# AJH_module_tester-v02_11.net
KiCad netlist of a schematic drawn in EAGLE
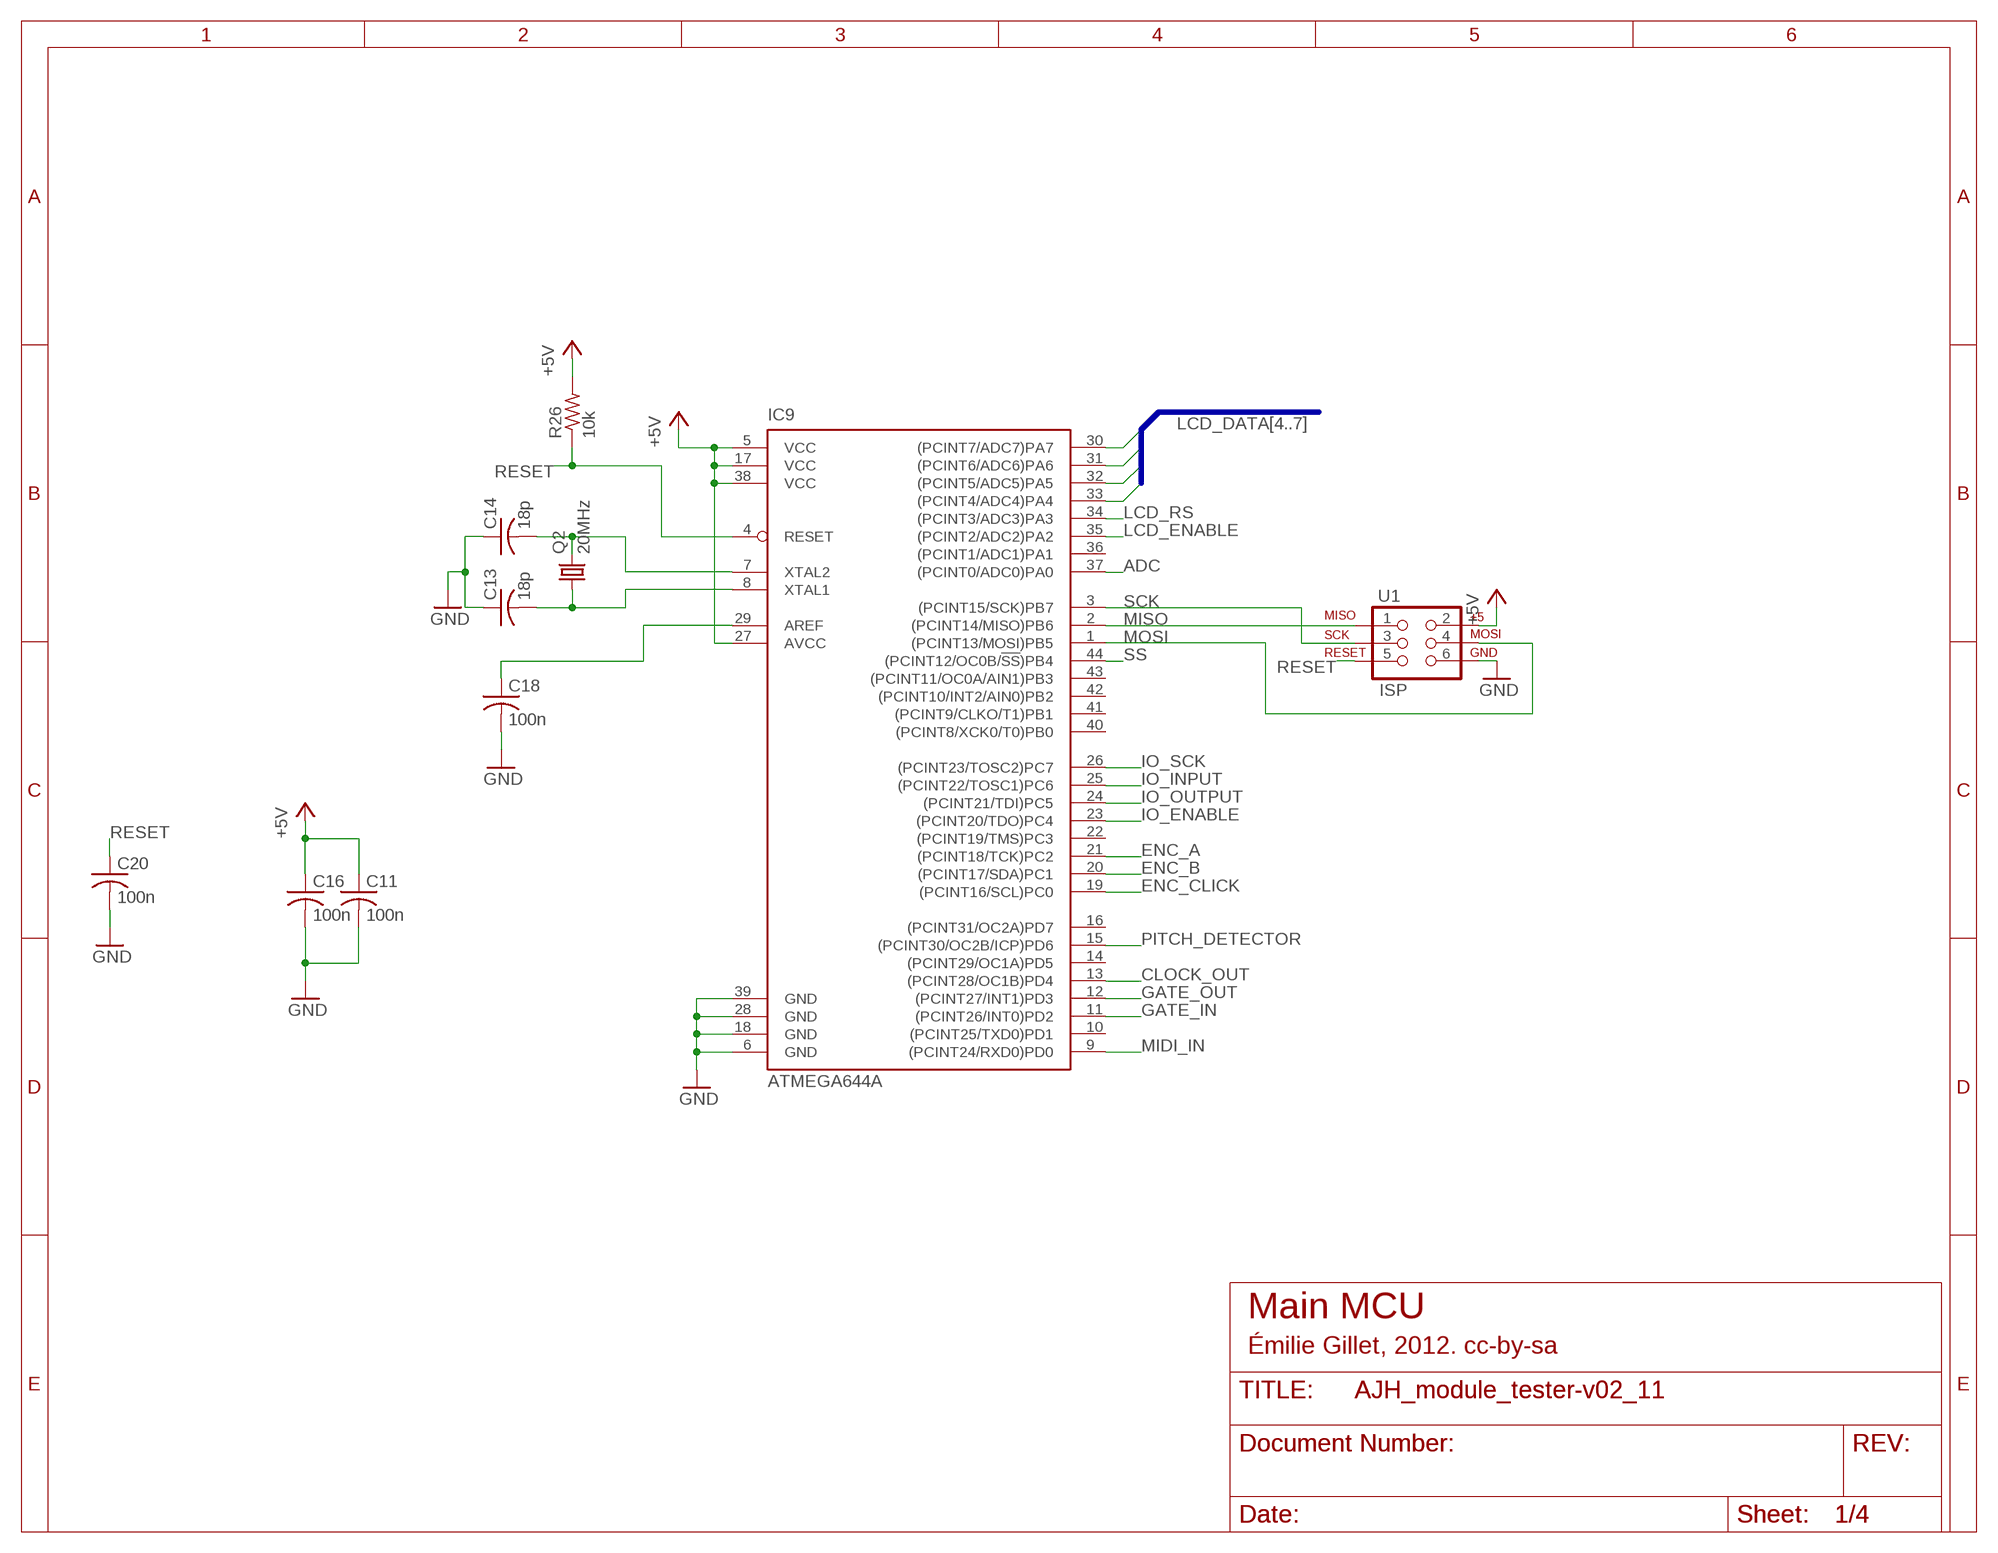
[diagram p0: schematic, sheet 1]
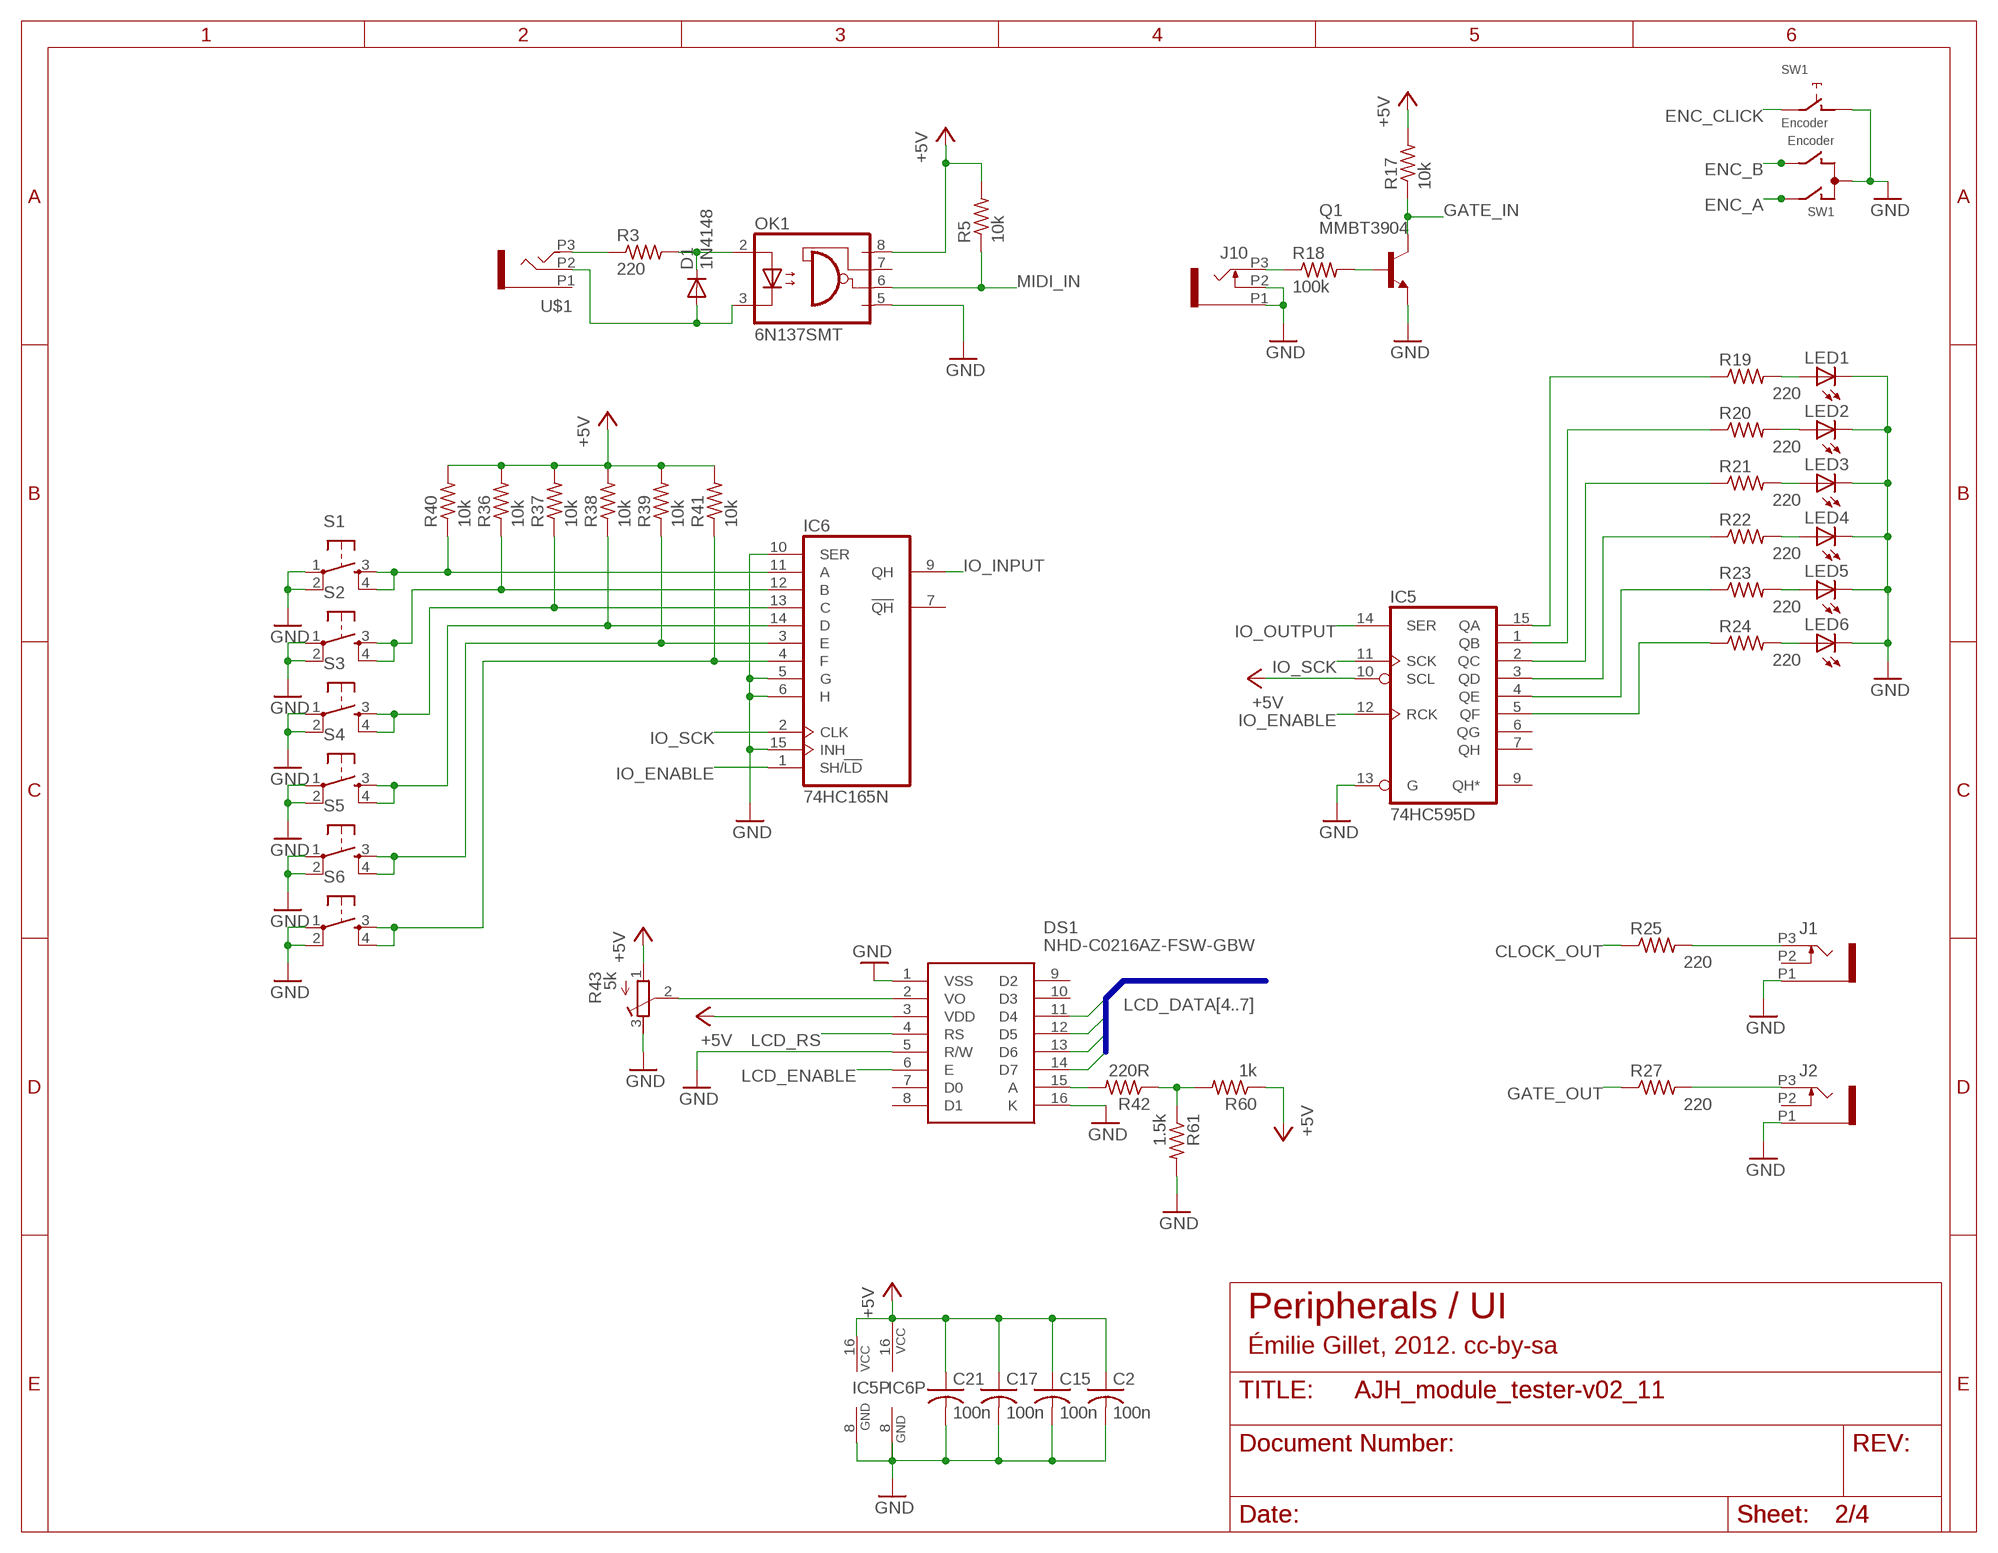
[diagram p1: schematic, sheet 2]
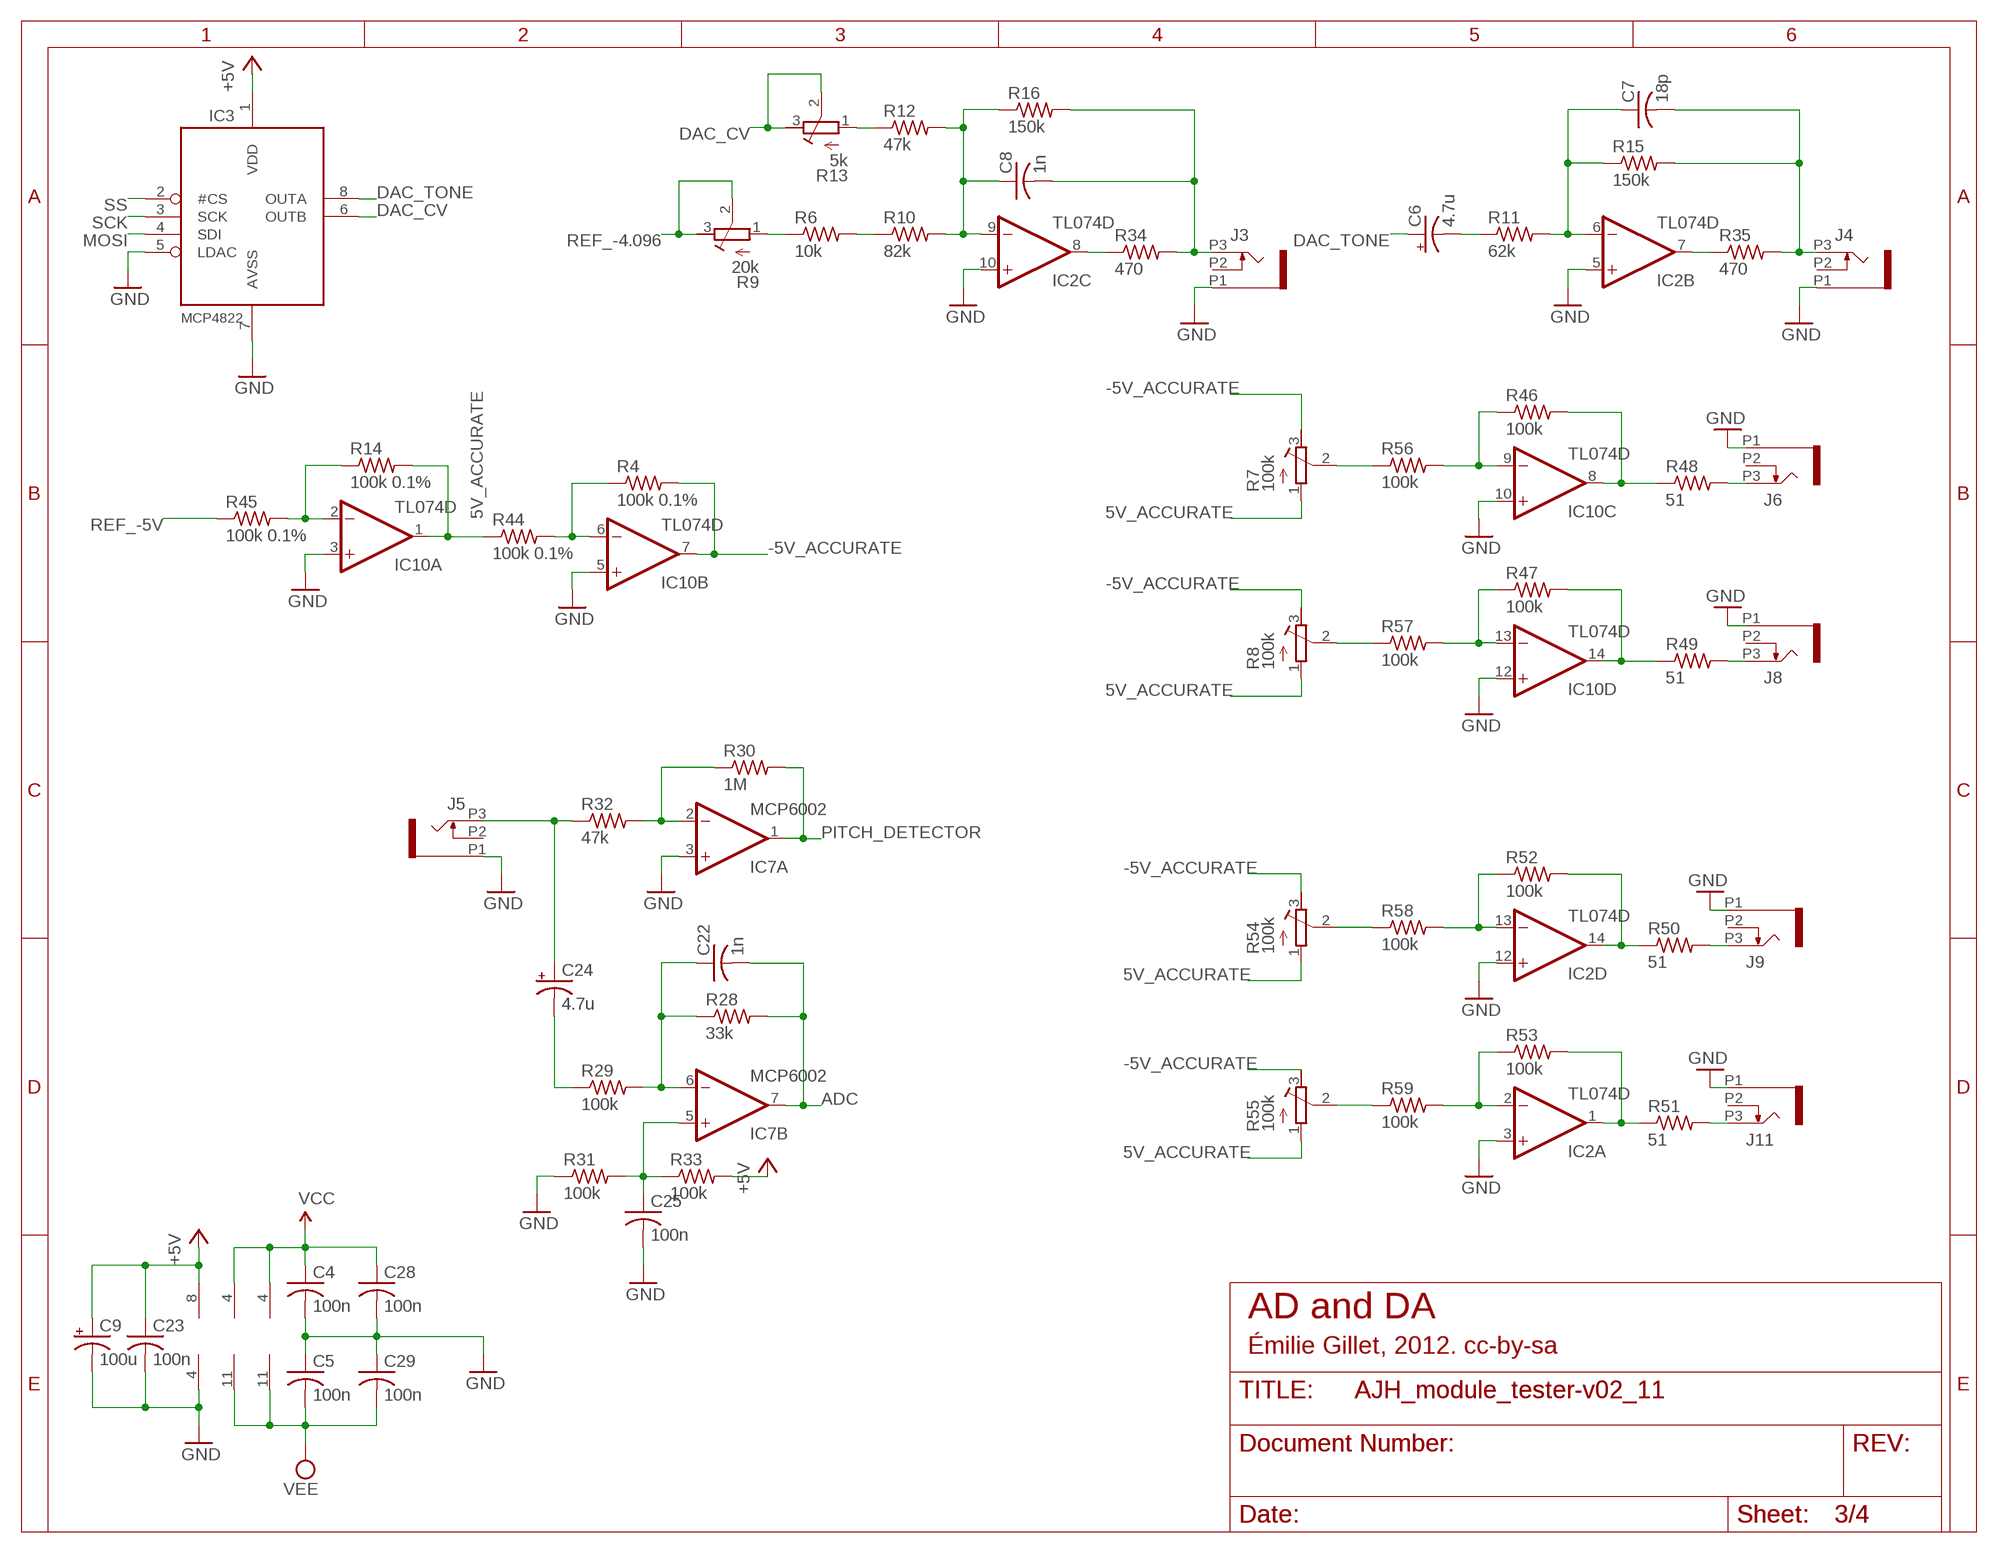
[diagram p2: schematic, sheet 3]
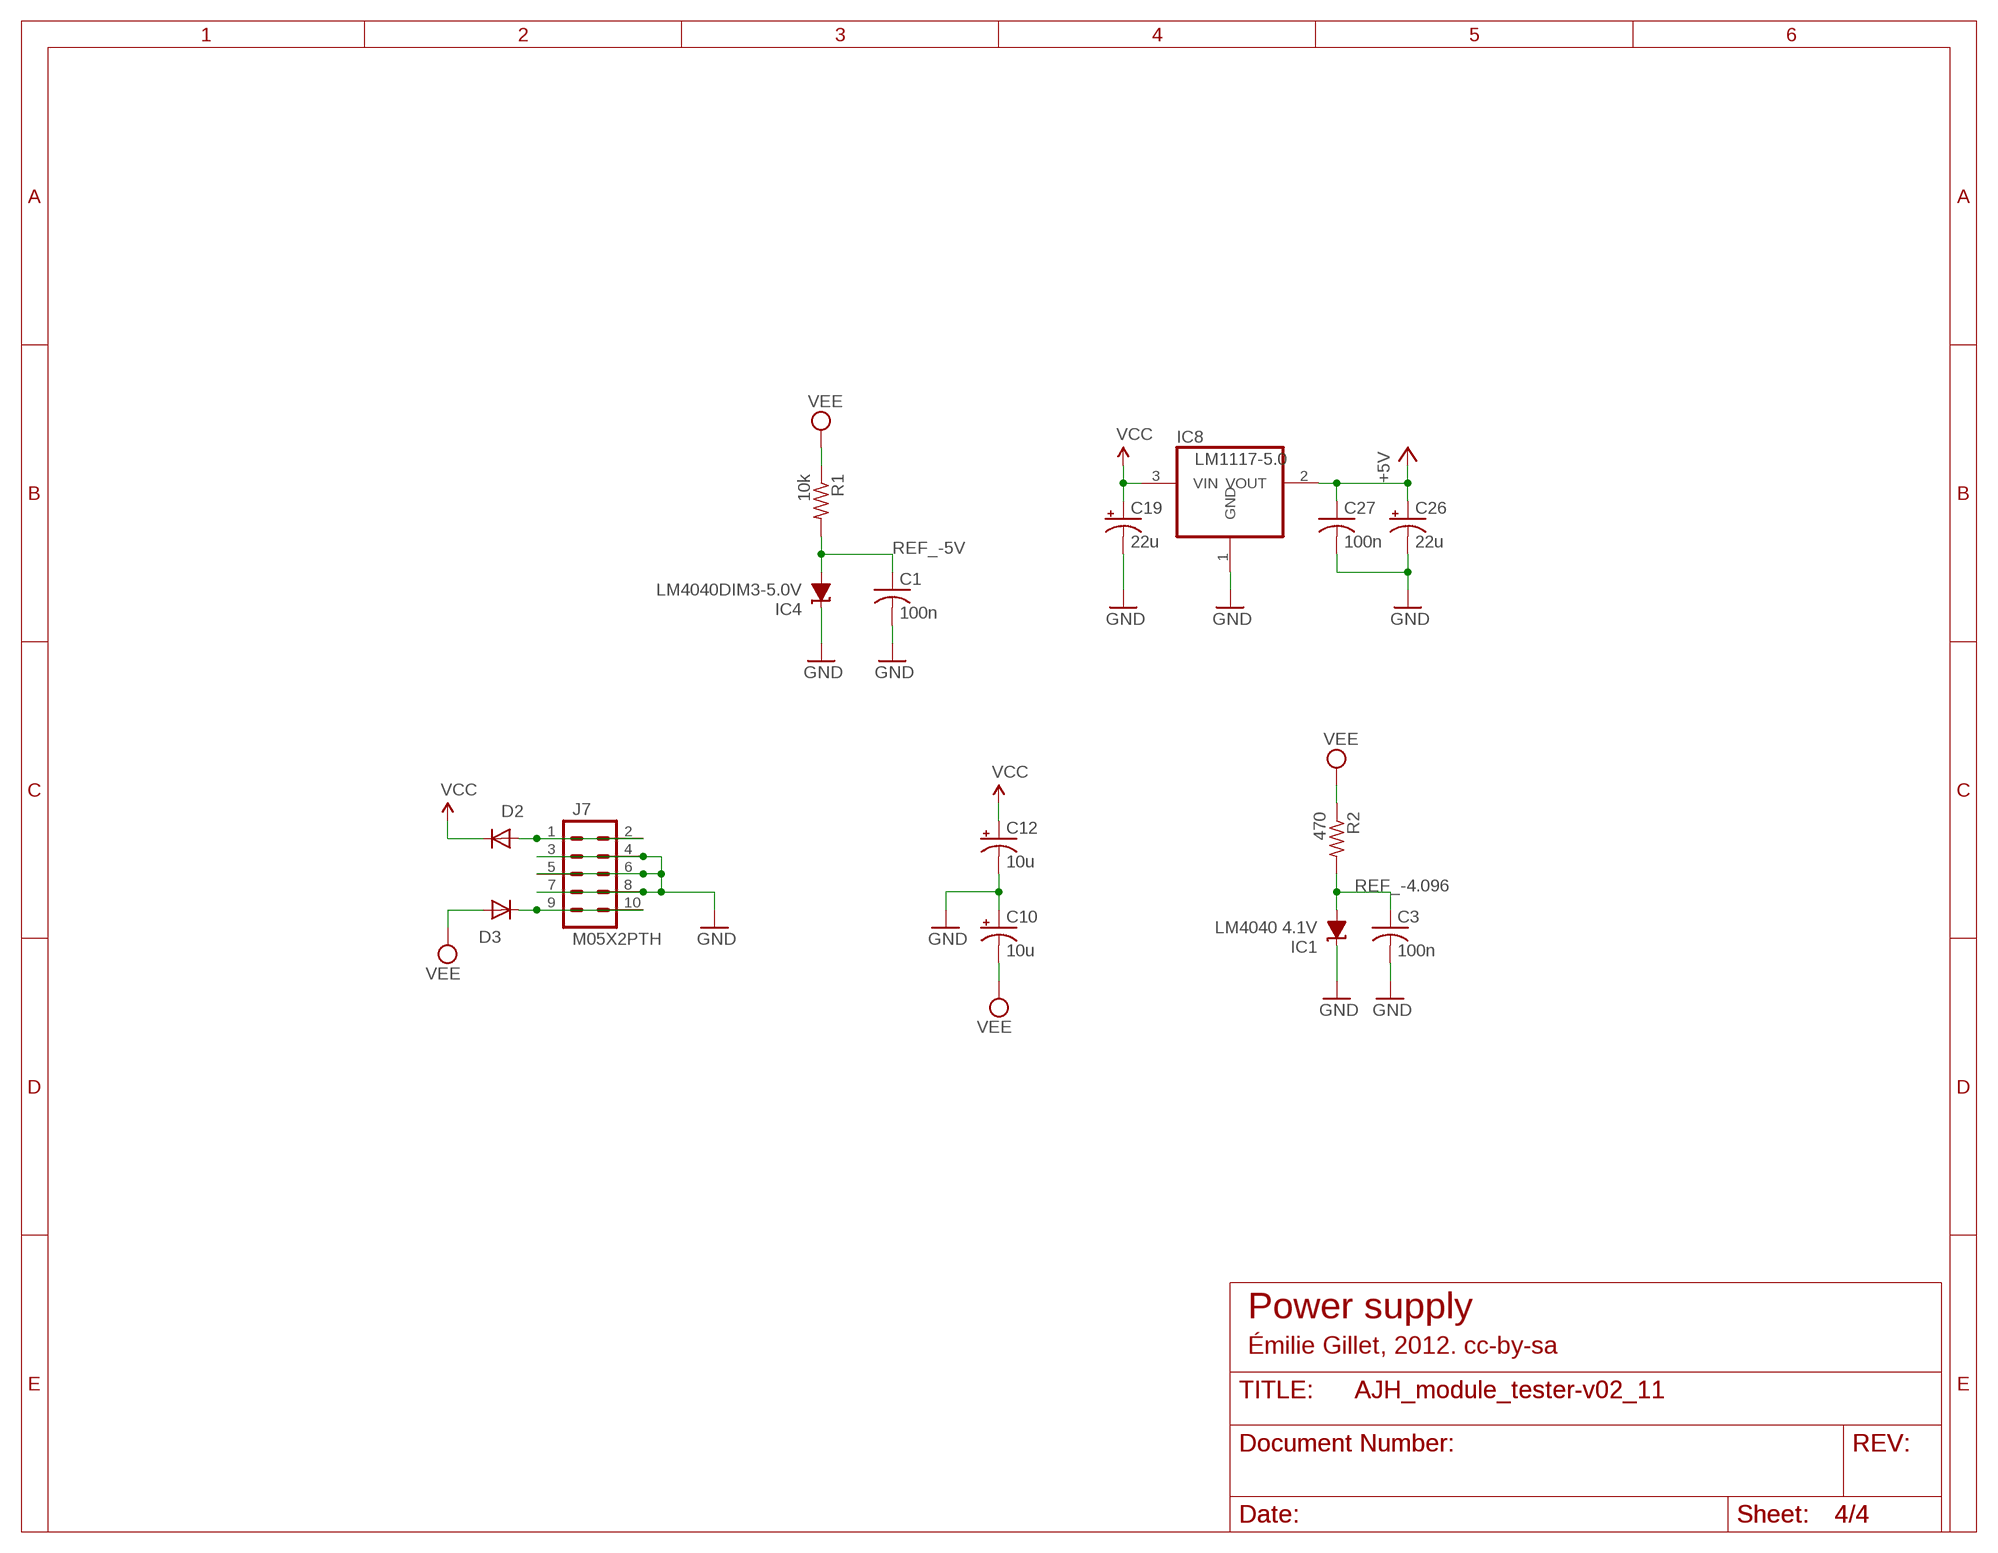
[diagram p3: schematic, sheet 4]

(export (version "E")
  (design (tool "Eeschema 10.0.6"))
  (components
    (comp (ref "C4")
      (value "100n")
      (footprint "eagle-import:C0603")
      (libsource (lib "eagle-import") (part "C-USC0603"))
    )
    (comp (ref "C5")
      (value "100n")
      (footprint "eagle-import:C0603")
      (libsource (lib "eagle-import") (part "C-USC0603"))
    )
    (comp (ref "C6")
      (value "4.7u")
      (footprint "eagle-import:PANASONIC_A")
      (libsource (lib "eagle-import") (part "CPOL-USA"))
    )
    (comp (ref "C7")
      (value "18p")
      (footprint "eagle-import:C0603")
      (libsource (lib "eagle-import") (part "C-USC0603"))
    )
    (comp (ref "C8")
      (value "1n")
      (footprint "eagle-import:C0603")
      (libsource (lib "eagle-import") (part "C-USC0603"))
    )
    (comp (ref "C9")
      (value "100u")
      (footprint "eagle-import:PANASONIC_A")
      (libsource (lib "eagle-import") (part "CPOL-USA"))
    )
    (comp (ref "C22")
      (value "1n")
      (footprint "eagle-import:C0603")
      (libsource (lib "eagle-import") (part "C-USC0603"))
    )
    (comp (ref "C23")
      (value "100n")
      (footprint "eagle-import:C0603")
      (libsource (lib "eagle-import") (part "C-USC0603"))
    )
    (comp (ref "C24")
      (value "4.7u")
      (footprint "eagle-import:PANASONIC_A")
      (libsource (lib "eagle-import") (part "CPOL-USA"))
    )
    (comp (ref "C25")
      (value "100n")
      (footprint "eagle-import:C0603")
      (libsource (lib "eagle-import") (part "C-USC0603"))
    )
    (comp (ref "C28")
      (value "100n")
      (footprint "eagle-import:C0603")
      (libsource (lib "eagle-import") (part "C-USC0603"))
    )
    (comp (ref "C29")
      (value "100n")
      (footprint "eagle-import:C0603")
      (libsource (lib "eagle-import") (part "C-USC0603"))
    )
    (comp (ref "IC2")
      (value "TL074D")
      (footprint "eagle-import:SO14")
      (libsource (lib "eagle-import") (part "TL074D"))
    )
    (comp (ref "IC3")
      (value "MCP4822SO08")
      (footprint "eagle-import:SO08")
      (libsource (lib "eagle-import") (part "MCP4822SO08"))
    )
    (comp (ref "IC7")
      (value "MCP6002")
      (footprint "eagle-import:SO08")
      (libsource (lib "eagle-import") (part "TL072D"))
    )
    (comp (ref "IC10")
      (value "TL074D")
      (footprint "eagle-import:SO14")
      (libsource (lib "eagle-import") (part "TL074D"))
    )
    (comp (ref "J3")
      (value "PJ301_THONKICONN6")
      (footprint "eagle-import:WQP_PJ_301M6")
      (libsource (lib "eagle-import") (part "PJ301_THONKICONN6"))
    )
    (comp (ref "J4")
      (value "PJ301_THONKICONN6")
      (footprint "eagle-import:WQP_PJ_301M6")
      (libsource (lib "eagle-import") (part "PJ301_THONKICONN6"))
    )
    (comp (ref "J5")
      (value "PJ301_THONKICONN6")
      (footprint "eagle-import:WQP_PJ_301M6")
      (libsource (lib "eagle-import") (part "PJ301_THONKICONN6"))
    )
    (comp (ref "J6")
      (value "PJ301_THONKICONN6")
      (footprint "eagle-import:WQP_PJ_301M6")
      (libsource (lib "eagle-import") (part "PJ301_THONKICONN6"))
    )
    (comp (ref "J8")
      (value "PJ301_THONKICONN6")
      (footprint "eagle-import:WQP_PJ_301M6")
      (libsource (lib "eagle-import") (part "PJ301_THONKICONN6"))
    )
    (comp (ref "J9")
      (value "PJ301_THONKICONN6")
      (footprint "eagle-import:WQP_PJ_301M6")
      (libsource (lib "eagle-import") (part "PJ301_THONKICONN6"))
    )
    (comp (ref "J11")
      (value "PJ301_THONKICONN6")
      (footprint "eagle-import:WQP_PJ_301M6")
      (libsource (lib "eagle-import") (part "PJ301_THONKICONN6"))
    )
    (comp (ref "R4")
      (value "100k 0.1%")
      (footprint "eagle-import:R0603")
      (libsource (lib "eagle-import") (part "R-US_R0603"))
    )
    (comp (ref "R6")
      (value "10k")
      (footprint "eagle-import:R0603")
      (libsource (lib "eagle-import") (part "R-US_R0603"))
    )
    (comp (ref "R7")
      (value "100k")
      (footprint "eagle-import:RTRIM3296W")
      (libsource (lib "eagle-import") (part "R-TRIMM3296W"))
    )
    (comp (ref "R8")
      (value "100k")
      (footprint "eagle-import:RTRIM3296W")
      (libsource (lib "eagle-import") (part "R-TRIMM3296W"))
    )
    (comp (ref "R9")
      (value "20k")
      (footprint "eagle-import:RTRIM3296W")
      (libsource (lib "eagle-import") (part "R-TRIMM3296W"))
    )
    (comp (ref "R10")
      (value "82k")
      (footprint "eagle-import:R0603")
      (libsource (lib "eagle-import") (part "R-US_R0603"))
    )
    (comp (ref "R11")
      (value "62k")
      (footprint "eagle-import:R0603")
      (libsource (lib "eagle-import") (part "R-US_R0603"))
    )
    (comp (ref "R12")
      (value "47k")
      (footprint "eagle-import:R0603")
      (libsource (lib "eagle-import") (part "R-US_R0603"))
    )
    (comp (ref "R13")
      (value "5k")
      (footprint "eagle-import:RTRIM3296W")
      (libsource (lib "eagle-import") (part "R-TRIMM3296W"))
    )
    (comp (ref "R14")
      (value "100k 0.1%")
      (footprint "eagle-import:R0603")
      (libsource (lib "eagle-import") (part "R-US_R0603"))
    )
    (comp (ref "R15")
      (value "150k")
      (footprint "eagle-import:R0603")
      (libsource (lib "eagle-import") (part "R-US_R0603"))
    )
    (comp (ref "R16")
      (value "150k")
      (footprint "eagle-import:R0603")
      (libsource (lib "eagle-import") (part "R-US_R0603"))
    )
    (comp (ref "R28")
      (value "33k")
      (footprint "eagle-import:R0603")
      (libsource (lib "eagle-import") (part "R-US_R0603"))
    )
    (comp (ref "R29")
      (value "100k")
      (footprint "eagle-import:R0603")
      (libsource (lib "eagle-import") (part "R-US_R0603"))
    )
    (comp (ref "R30")
      (value "1M")
      (footprint "eagle-import:R0603")
      (libsource (lib "eagle-import") (part "R-US_R0603"))
    )
    (comp (ref "R31")
      (value "100k")
      (footprint "eagle-import:R0603")
      (libsource (lib "eagle-import") (part "R-US_R0603"))
    )
    (comp (ref "R32")
      (value "47k")
      (footprint "eagle-import:R0603")
      (libsource (lib "eagle-import") (part "R-US_R0603"))
    )
    (comp (ref "R33")
      (value "100k")
      (footprint "eagle-import:R0603")
      (libsource (lib "eagle-import") (part "R-US_R0603"))
    )
    (comp (ref "R34")
      (value "470")
      (footprint "eagle-import:R0603")
      (libsource (lib "eagle-import") (part "R-US_R0603"))
    )
    (comp (ref "R35")
      (value "470")
      (footprint "eagle-import:R0603")
      (libsource (lib "eagle-import") (part "R-US_R0603"))
    )
    (comp (ref "R44")
      (value "100k 0.1%")
      (footprint "eagle-import:R0603")
      (libsource (lib "eagle-import") (part "R-US_R0603"))
    )
    (comp (ref "R45")
      (value "100k 0.1%")
      (footprint "eagle-import:R0603")
      (libsource (lib "eagle-import") (part "R-US_R0603"))
    )
    (comp (ref "R46")
      (value "100k")
      (footprint "eagle-import:R0603")
      (libsource (lib "eagle-import") (part "R-US_R0603"))
    )
    (comp (ref "R47")
      (value "100k")
      (footprint "eagle-import:R0603")
      (libsource (lib "eagle-import") (part "R-US_R0603"))
    )
    (comp (ref "R48")
      (value "51")
      (footprint "eagle-import:R0603")
      (libsource (lib "eagle-import") (part "R-US_R0603"))
    )
    (comp (ref "R49")
      (value "51")
      (footprint "eagle-import:R0603")
      (libsource (lib "eagle-import") (part "R-US_R0603"))
    )
    (comp (ref "R50")
      (value "51")
      (footprint "eagle-import:R0603")
      (libsource (lib "eagle-import") (part "R-US_R0603"))
    )
    (comp (ref "R51")
      (value "51")
      (footprint "eagle-import:R0603")
      (libsource (lib "eagle-import") (part "R-US_R0603"))
    )
    (comp (ref "R52")
      (value "100k")
      (footprint "eagle-import:R0603")
      (libsource (lib "eagle-import") (part "R-US_R0603"))
    )
    (comp (ref "R53")
      (value "100k")
      (footprint "eagle-import:R0603")
      (libsource (lib "eagle-import") (part "R-US_R0603"))
    )
    (comp (ref "R54")
      (value "100k")
      (footprint "eagle-import:RTRIM3296W")
      (libsource (lib "eagle-import") (part "R-TRIMM3296W"))
    )
    (comp (ref "R55")
      (value "100k")
      (footprint "eagle-import:RTRIM3296W")
      (libsource (lib "eagle-import") (part "R-TRIMM3296W"))
    )
    (comp (ref "R56")
      (value "100k")
      (footprint "eagle-import:R0603")
      (libsource (lib "eagle-import") (part "R-US_R0603"))
    )
    (comp (ref "R57")
      (value "100k")
      (footprint "eagle-import:R0603")
      (libsource (lib "eagle-import") (part "R-US_R0603"))
    )
    (comp (ref "R58")
      (value "100k")
      (footprint "eagle-import:R0603")
      (libsource (lib "eagle-import") (part "R-US_R0603"))
    )
    (comp (ref "R59")
      (value "100k")
      (footprint "eagle-import:R0603")
      (libsource (lib "eagle-import") (part "R-US_R0603"))
    )
    (comp (ref "C1")
      (value "100n")
      (footprint "eagle-import:C0603")
      (libsource (lib "eagle-import") (part "C-USC0603"))
    )
    (comp (ref "C3")
      (value "100n")
      (footprint "eagle-import:C0603")
      (libsource (lib "eagle-import") (part "C-USC0603"))
    )
    (comp (ref "C10")
      (value "10u")
      (footprint "eagle-import:PANASONIC_A")
      (libsource (lib "eagle-import") (part "CPOL-USA"))
    )
    (comp (ref "C12")
      (value "10u")
      (footprint "eagle-import:PANASONIC_A")
      (libsource (lib "eagle-import") (part "CPOL-USA"))
    )
    (comp (ref "C19")
      (value "22u")
      (footprint "eagle-import:PANASONIC_C")
      (libsource (lib "eagle-import") (part "CPOL-USC"))
    )
    (comp (ref "C26")
      (value "22u")
      (footprint "eagle-import:PANASONIC_C")
      (libsource (lib "eagle-import") (part "CPOL-USC"))
    )
    (comp (ref "C27")
      (value "100n")
      (footprint "eagle-import:C0603")
      (libsource (lib "eagle-import") (part "C-USC0603"))
    )
    (comp (ref "D2")
      (value "1N5819HW")
      (footprint "eagle-import:SOD123")
      (libsource (lib "eagle-import") (part "DIODE-SOD123"))
    )
    (comp (ref "D3")
      (value "1N5819HW")
      (footprint "eagle-import:SOD123")
      (libsource (lib "eagle-import") (part "DIODE-SOD123"))
    )
    (comp (ref "IC1")
      (value "LM4040 4.1V")
      (footprint "eagle-import:DBZ_R-PDSO-G3")
      (libsource (lib "eagle-import") (part "LM4041DBZC12"))
    )
    (comp (ref "IC4")
      (value "LM4040DIM3-5.0V")
      (footprint "eagle-import:DBZ_R-PDSO-G3")
      (libsource (lib "eagle-import") (part "LM4041DBZC12"))
    )
    (comp (ref "IC8")
      (value "LM1117-5.0")
      (footprint "eagle-import:SOT223")
      (libsource (lib "eagle-import") (part "REG1117"))
    )
    (comp (ref "J7")
      (value "M05X2PTH")
      (footprint "eagle-import:AVR_ICSP")
      (libsource (lib "eagle-import") (part "M05X2PTH"))
    )
    (comp (ref "R1")
      (value "10k")
      (footprint "eagle-import:R0603")
      (libsource (lib "eagle-import") (part "resistor_R-US_R0603"))
    )
    (comp (ref "R2")
      (value "470")
      (footprint "eagle-import:R0603")
      (libsource (lib "eagle-import") (part "resistor_R-US_R0603"))
    )
    (comp (ref "C11")
      (value "100n")
      (footprint "eagle-import:C0603")
      (libsource (lib "eagle-import") (part "C-USC0603"))
    )
    (comp (ref "C13")
      (value "18p")
      (footprint "eagle-import:C0603")
      (libsource (lib "eagle-import") (part "C-USC0603"))
    )
    (comp (ref "C14")
      (value "18p")
      (footprint "eagle-import:C0603")
      (libsource (lib "eagle-import") (part "C-USC0603"))
    )
    (comp (ref "C16")
      (value "100n")
      (footprint "eagle-import:C0603")
      (libsource (lib "eagle-import") (part "C-USC0603"))
    )
    (comp (ref "C18")
      (value "100n")
      (footprint "eagle-import:C0603")
      (libsource (lib "eagle-import") (part "C-USC0603"))
    )
    (comp (ref "C20")
      (value "100n")
      (footprint "eagle-import:C0603")
      (libsource (lib "eagle-import") (part "C-USC0603"))
    )
    (comp (ref "IC9")
      (value "ATMEGA644A")
      (footprint "eagle-import:TQFP44")
      (fields (field (name "MPN") "ATMEGA644PV-10AU"))
      (libsource (lib "eagle-import") (part "ATMEGA644A"))
    )
    (comp (ref "Q2")
      (value "20MHz")
      (footprint "eagle-import:HC49UP")
      (libsource (lib "eagle-import") (part "CRYSTALHC49UP"))
    )
    (comp (ref "R26")
      (value "10k")
      (footprint "eagle-import:R0603")
      (libsource (lib "eagle-import") (part "R-US_R0603"))
    )
    (comp (ref "U1")
      (value "ISP")
      (footprint "eagle-import:2X3")
      (libsource (lib "eagle-import") (part "AVR_SPI_PRG_6PTH"))
    )
    (comp (ref "C2")
      (value "100n")
      (footprint "eagle-import:C0603")
      (libsource (lib "eagle-import") (part "C-USC0603"))
    )
    (comp (ref "C15")
      (value "100n")
      (footprint "eagle-import:C0603")
      (libsource (lib "eagle-import") (part "C-USC0603"))
    )
    (comp (ref "C17")
      (value "100n")
      (footprint "eagle-import:C0603")
      (libsource (lib "eagle-import") (part "C-USC0603"))
    )
    (comp (ref "C21")
      (value "100n")
      (footprint "eagle-import:C0603")
      (libsource (lib "eagle-import") (part "C-USC0603"))
    )
    (comp (ref "D1")
      (value "1N4148")
      (footprint "eagle-import:SOD123")
      (libsource (lib "eagle-import") (part "DIODE-SOD123"))
    )
    (comp (ref "DS1")
      (value "NHD-C0216AZ-FSW-GBW")
      (footprint "eagle-import:NHDC0216AZFSWGBW")
      (fields (field (name "MOUSER_PART_NUMBER") "763-C0216AZ-FSW-GBW"))
      (libsource (lib "eagle-import") (part "NHD-C0216AZ-FSW-GBW"))
    )
    (comp (ref "IC5")
      (value "74HC595D")
      (footprint "eagle-import:SO16")
      (libsource (lib "eagle-import") (part "74595DHC"))
    )
    (comp (ref "IC6")
      (value "74HC165N")
      (footprint "eagle-import:SO16")
      (libsource (lib "eagle-import") (part "74165DLS"))
    )
    (comp (ref "J1")
      (value "PJ301_THONKICONN6")
      (footprint "eagle-import:WQP_PJ_301M6")
      (libsource (lib "eagle-import") (part "PJ301_THONKICONN6"))
    )
    (comp (ref "J2")
      (value "PJ301_THONKICONN6")
      (footprint "eagle-import:WQP_PJ_301M6")
      (libsource (lib "eagle-import") (part "PJ301_THONKICONN6"))
    )
    (comp (ref "J10")
      (value "PJ301_THONKICONN6")
      (footprint "eagle-import:WQP_PJ_301M6")
      (libsource (lib "eagle-import") (part "PJ301_THONKICONN6"))
    )
    (comp (ref "LED1")
      (value "LED3MM")
      (footprint "eagle-import:LED3MM")
      (libsource (lib "eagle-import") (part "LED3MM"))
    )
    (comp (ref "LED2")
      (value "LED3MM")
      (footprint "eagle-import:LED3MM")
      (libsource (lib "eagle-import") (part "LED3MM"))
    )
    (comp (ref "LED3")
      (value "LED3MM")
      (footprint "eagle-import:LED3MM")
      (libsource (lib "eagle-import") (part "LED3MM"))
    )
    (comp (ref "LED4")
      (value "LED3MM")
      (footprint "eagle-import:LED3MM")
      (libsource (lib "eagle-import") (part "LED3MM"))
    )
    (comp (ref "LED5")
      (value "LED3MM")
      (footprint "eagle-import:LED3MM")
      (libsource (lib "eagle-import") (part "LED3MM"))
    )
    (comp (ref "LED6")
      (value "LED3MM")
      (footprint "eagle-import:LED3MM")
      (libsource (lib "eagle-import") (part "LED3MM"))
    )
    (comp (ref "OK1")
      (value "6N137SMT")
      (footprint "eagle-import:DIL8-SMD")
      (libsource (lib "eagle-import") (part "6N137SMT"))
    )
    (comp (ref "Q1")
      (value "MMBT3904")
      (footprint "eagle-import:SOT23-BEC")
      (libsource (lib "eagle-import") (part "-NPN-SOT23-BECMMBT3904LT1"))
    )
    (comp (ref "R3")
      (value "220")
      (footprint "eagle-import:R0603")
      (libsource (lib "eagle-import") (part "R-US_R0603"))
    )
    (comp (ref "R5")
      (value "10k")
      (footprint "eagle-import:R0603")
      (libsource (lib "eagle-import") (part "R-US_R0603"))
    )
    (comp (ref "R17")
      (value "10k")
      (footprint "eagle-import:R0603")
      (libsource (lib "eagle-import") (part "R-US_R0603"))
    )
    (comp (ref "R18")
      (value "100k")
      (footprint "eagle-import:R0603")
      (libsource (lib "eagle-import") (part "R-US_R0603"))
    )
    (comp (ref "R19")
      (value "220")
      (footprint "eagle-import:R0603")
      (libsource (lib "eagle-import") (part "R-US_R0603"))
    )
    (comp (ref "R20")
      (value "220")
      (footprint "eagle-import:R0603")
      (libsource (lib "eagle-import") (part "R-US_R0603"))
    )
    (comp (ref "R21")
      (value "220")
      (footprint "eagle-import:R0603")
      (libsource (lib "eagle-import") (part "R-US_R0603"))
    )
    (comp (ref "R22")
      (value "220")
      (footprint "eagle-import:R0603")
      (libsource (lib "eagle-import") (part "R-US_R0603"))
    )
    (comp (ref "R23")
      (value "220")
      (footprint "eagle-import:R0603")
      (libsource (lib "eagle-import") (part "R-US_R0603"))
    )
    (comp (ref "R24")
      (value "220")
      (footprint "eagle-import:R0603")
      (libsource (lib "eagle-import") (part "R-US_R0603"))
    )
    (comp (ref "R25")
      (value "220")
      (footprint "eagle-import:R0603")
      (libsource (lib "eagle-import") (part "R-US_R0603"))
    )
    (comp (ref "R27")
      (value "220")
      (footprint "eagle-import:R0603")
      (libsource (lib "eagle-import") (part "R-US_R0603"))
    )
    (comp (ref "R36")
      (value "10k")
      (footprint "eagle-import:R0603")
      (libsource (lib "eagle-import") (part "R-US_R0603"))
    )
    (comp (ref "R37")
      (value "10k")
      (footprint "eagle-import:R0603")
      (libsource (lib "eagle-import") (part "R-US_R0603"))
    )
    (comp (ref "R38")
      (value "10k")
      (footprint "eagle-import:R0603")
      (libsource (lib "eagle-import") (part "R-US_R0603"))
    )
    (comp (ref "R39")
      (value "10k")
      (footprint "eagle-import:R0603")
      (libsource (lib "eagle-import") (part "R-US_R0603"))
    )
    (comp (ref "R40")
      (value "10k")
      (footprint "eagle-import:R0603")
      (libsource (lib "eagle-import") (part "R-US_R0603"))
    )
    (comp (ref "R41")
      (value "10k")
      (footprint "eagle-import:R0603")
      (libsource (lib "eagle-import") (part "R-US_R0603"))
    )
    (comp (ref "R42")
      (value "220R")
      (footprint "eagle-import:R0603")
      (libsource (lib "eagle-import") (part "R-US_R0603"))
    )
    (comp (ref "R43")
      (value "5k")
      (footprint "eagle-import:RTRIM3339P")
      (libsource (lib "eagle-import") (part "R-TRIMM3339P"))
    )
    (comp (ref "R60")
      (value "1k")
      (footprint "eagle-import:R0603")
      (libsource (lib "eagle-import") (part "R-US_R0603"))
    )
    (comp (ref "R61")
      (value "1.5k")
      (footprint "eagle-import:R0603")
      (libsource (lib "eagle-import") (part "R-US_R0603"))
    )
    (comp (ref "S1")
      (value "TAC_SWITCHPTH")
      (footprint "eagle-import:TACTILE-PTH")
      (libsource (lib "eagle-import") (part "TAC_SWITCHPTH"))
    )
    (comp (ref "S2")
      (value "TAC_SWITCHPTH")
      (footprint "eagle-import:TACTILE-PTH")
      (libsource (lib "eagle-import") (part "TAC_SWITCHPTH"))
    )
    (comp (ref "S3")
      (value "TAC_SWITCHPTH")
      (footprint "eagle-import:TACTILE-PTH")
      (libsource (lib "eagle-import") (part "TAC_SWITCHPTH"))
    )
    (comp (ref "S4")
      (value "TAC_SWITCHPTH")
      (footprint "eagle-import:TACTILE-PTH")
      (libsource (lib "eagle-import") (part "TAC_SWITCHPTH"))
    )
    (comp (ref "S5")
      (value "TAC_SWITCHPTH")
      (footprint "eagle-import:TACTILE-PTH")
      (libsource (lib "eagle-import") (part "TAC_SWITCHPTH"))
    )
    (comp (ref "S6")
      (value "TAC_SWITCHPTH")
      (footprint "eagle-import:TACTILE-PTH")
      (libsource (lib "eagle-import") (part "TAC_SWITCHPTH"))
    )
    (comp (ref "SW1")
      (value "Encoder")
      (footprint "eagle-import:ALPS_EC12E_SW")
      (libsource (lib "eagle-import") (part "EC12E_SW"))
    )
    (comp (ref "U$1")
      (value "PJ366ST")
      (footprint "eagle-import:WQP_PJ_301M8")
      (libsource (lib "eagle-import") (part "PJ366ST"))
    )
  )
  (nets
    (net (code "1") (name "+5V") (class "Default")
      (node (ref "C11") (pin "1") (pinfunction "1_1") (pintype "passive"))
      (node (ref "C15") (pin "1") (pinfunction "1_1") (pintype "passive"))
      (node (ref "C16") (pin "1") (pinfunction "1_1") (pintype "passive"))
      (node (ref "C17") (pin "1") (pinfunction "1_1") (pintype "passive"))
      (node (ref "C2") (pin "1") (pinfunction "1_1") (pintype "passive"))
      (node (ref "C21") (pin "1") (pinfunction "1_1") (pintype "passive"))
      (node (ref "C23") (pin "1") (pinfunction "1_1") (pintype "passive"))
      (node (ref "C26") (pin "+") (pinfunction "+_+") (pintype "passive"))
      (node (ref "C27") (pin "1") (pinfunction "1_1") (pintype "passive"))
      (node (ref "C9") (pin "+") (pinfunction "+_+") (pintype "passive"))
      (node (ref "DS1") (pin "3") (pinfunction "VDD_3") (pintype "bidirectional"))
      (node (ref "IC3") (pin "1") (pinfunction "VDD_1") (pintype "power_in"))
      (node (ref "IC5") (pin "10") (pinfunction "SCL_10") (pintype "input"))
      (node (ref "IC5") (pin "16") (pinfunction "VCC_16") (pintype "power_in"))
      (node (ref "IC6") (pin "16") (pinfunction "VCC_16") (pintype "power_in"))
      (node (ref "IC7") (pin "8") (pinfunction "V+_8") (pintype "power_in"))
      (node (ref "IC8") (pin "2") (pinfunction "VOUT_2") (pintype "output"))
      (node (ref "IC9") (pin "17") (pinfunction "VCC_17") (pintype "power_in"))
      (node (ref "IC9") (pin "27") (pinfunction "AVCC_27") (pintype "power_in"))
      (node (ref "IC9") (pin "38") (pinfunction "VCC_38") (pintype "power_in"))
      (node (ref "IC9") (pin "5") (pinfunction "VCC_5") (pintype "power_in"))
      (node (ref "OK1") (pin "8") (pinfunction "VCC_8") (pintype "passive"))
      (node (ref "R17") (pin "2") (pinfunction "2_2") (pintype "passive"))
      (node (ref "R26") (pin "2") (pinfunction "2_2") (pintype "passive"))
      (node (ref "R33") (pin "2") (pinfunction "2_2") (pintype "passive"))
      (node (ref "R36") (pin "2") (pinfunction "2_2") (pintype "passive"))
      (node (ref "R37") (pin "2") (pinfunction "2_2") (pintype "passive"))
      (node (ref "R38") (pin "2") (pinfunction "2_2") (pintype "passive"))
      (node (ref "R39") (pin "2") (pinfunction "2_2") (pintype "passive"))
      (node (ref "R40") (pin "2") (pinfunction "2_2") (pintype "passive"))
      (node (ref "R41") (pin "2") (pinfunction "2_2") (pintype "passive"))
      (node (ref "R43") (pin "1") (pinfunction "E_1") (pintype "passive"))
      (node (ref "R5") (pin "2") (pinfunction "2_2") (pintype "passive"))
      (node (ref "R60") (pin "1") (pinfunction "1_1") (pintype "passive"))
      (node (ref "U1") (pin "2") (pinfunction "2_2") (pintype "passive"))
    )
    (net (code "2") (name "-5V_ACCURATE") (class "Default")
      (node (ref "IC10") (pin "7") (pinfunction "OUT_7") (pintype "output"))
      (node (ref "R4") (pin "2") (pinfunction "2_2") (pintype "passive"))
      (node (ref "R54") (pin "3") (pinfunction "A_3") (pintype "passive"))
      (node (ref "R55") (pin "3") (pinfunction "A_3") (pintype "passive"))
      (node (ref "R7") (pin "3") (pinfunction "A_3") (pintype "passive"))
      (node (ref "R8") (pin "3") (pinfunction "A_3") (pintype "passive"))
    )
    (net (code "5") (name "5V_ACCURATE") (class "Default")
      (node (ref "IC10") (pin "1") (pinfunction "OUT_1") (pintype "output"))
      (node (ref "R14") (pin "2") (pinfunction "2_2") (pintype "passive"))
      (node (ref "R44") (pin "1") (pinfunction "1_1") (pintype "passive"))
      (node (ref "R54") (pin "1") (pinfunction "E_1") (pintype "passive"))
      (node (ref "R55") (pin "1") (pinfunction "E_1") (pintype "passive"))
      (node (ref "R7") (pin "1") (pinfunction "E_1") (pintype "passive"))
      (node (ref "R8") (pin "1") (pinfunction "E_1") (pintype "passive"))
    )
    (net (code "6") (name "ADC") (class "Default")
      (node (ref "C22") (pin "2") (pinfunction "2_2") (pintype "passive"))
      (node (ref "IC7") (pin "7") (pinfunction "OUT_7") (pintype "output"))
      (node (ref "IC9") (pin "37") (pinfunction "(PCINT0/ADC0)PA0_37") (pintype "bidirectional"))
      (node (ref "R28") (pin "2") (pinfunction "2_2") (pintype "passive"))
    )
    (net (code "7") (name "CLOCK_OUT") (class "Default")
      (node (ref "IC9") (pin "13") (pinfunction "(PCINT28/OC1B)PD4_13") (pintype "bidirectional"))
      (node (ref "R25") (pin "1") (pinfunction "1_1") (pintype "passive"))
    )
    (net (code "8") (name "DAC_CV") (class "Default")
      (node (ref "IC3") (pin "6") (pinfunction "OUTB_6") (pintype "output"))
      (node (ref "R13") (pin "2") (pinfunction "S_2") (pintype "passive"))
      (node (ref "R13") (pin "3") (pinfunction "A_3") (pintype "passive"))
    )
    (net (code "9") (name "DAC_TONE") (class "Default")
      (node (ref "C6") (pin "+") (pinfunction "+_+") (pintype "passive"))
      (node (ref "IC3") (pin "8") (pinfunction "OUTA_8") (pintype "output"))
    )
    (net (code "10") (name "ENC_A") (class "Default")
      (node (ref "IC9") (pin "21") (pinfunction "(PCINT18/TCK)PC2_21") (pintype "output"))
      (node (ref "SW1") (pin "A") (pinfunction "A_A") (pintype "passive"))
    )
    (net (code "11") (name "ENC_B") (class "Default")
      (node (ref "IC9") (pin "20") (pinfunction "(PCINT17/SDA)PC1_20") (pintype "output"))
      (node (ref "SW1") (pin "B") (pinfunction "B_B") (pintype "passive"))
    )
    (net (code "12") (name "ENC_CLICK") (class "Default")
      (node (ref "IC9") (pin "19") (pinfunction "(PCINT16/SCL)PC0_19") (pintype "output"))
      (node (ref "SW1") (pin "E") (pinfunction "2_E") (pintype "passive"))
    )
    (net (code "13") (name "GATE_IN") (class "Default")
      (node (ref "IC9") (pin "11") (pinfunction "(PCINT26/INT0)PD2_11") (pintype "bidirectional"))
      (node (ref "Q1") (pin "C") (pinfunction "C_C") (pintype "passive"))
      (node (ref "R17") (pin "1") (pinfunction "1_1") (pintype "passive"))
    )
    (net (code "14") (name "GATE_OUT") (class "Default")
      (node (ref "IC9") (pin "12") (pinfunction "(PCINT27/INT1)PD3_12") (pintype "bidirectional"))
      (node (ref "R27") (pin "1") (pinfunction "1_1") (pintype "passive"))
    )
    (net (code "15") (name "GND") (class "Default")
      (node (ref "C1") (pin "2") (pinfunction "2_2") (pintype "passive"))
      (node (ref "C10") (pin "+") (pinfunction "+_+") (pintype "passive"))
      (node (ref "C11") (pin "2") (pinfunction "2_2") (pintype "passive"))
      (node (ref "C12") (pin "-") (pinfunction "-_-") (pintype "passive"))
      (node (ref "C13") (pin "1") (pinfunction "1_1") (pintype "passive"))
      (node (ref "C14") (pin "1") (pinfunction "1_1") (pintype "passive"))
      (node (ref "C15") (pin "2") (pinfunction "2_2") (pintype "passive"))
      (node (ref "C16") (pin "2") (pinfunction "2_2") (pintype "passive"))
      (node (ref "C17") (pin "2") (pinfunction "2_2") (pintype "passive"))
      (node (ref "C18") (pin "2") (pinfunction "2_2") (pintype "passive"))
      (node (ref "C19") (pin "-") (pinfunction "-_-") (pintype "passive"))
      (node (ref "C2") (pin "2") (pinfunction "2_2") (pintype "passive"))
      (node (ref "C20") (pin "2") (pinfunction "2_2") (pintype "passive"))
      (node (ref "C21") (pin "2") (pinfunction "2_2") (pintype "passive"))
      (node (ref "C23") (pin "2") (pinfunction "2_2") (pintype "passive"))
      (node (ref "C25") (pin "2") (pinfunction "2_2") (pintype "passive"))
      (node (ref "C26") (pin "-") (pinfunction "-_-") (pintype "passive"))
      (node (ref "C27") (pin "2") (pinfunction "2_2") (pintype "passive"))
      (node (ref "C28") (pin "2") (pinfunction "2_2") (pintype "passive"))
      (node (ref "C29") (pin "1") (pinfunction "1_1") (pintype "passive"))
      (node (ref "C3") (pin "2") (pinfunction "2_2") (pintype "passive"))
      (node (ref "C4") (pin "2") (pinfunction "2_2") (pintype "passive"))
      (node (ref "C5") (pin "1") (pinfunction "1_1") (pintype "passive"))
      (node (ref "C9") (pin "-") (pinfunction "-_-") (pintype "passive"))
      (node (ref "DS1") (pin "1") (pinfunction "VSS_1") (pintype "bidirectional"))
      (node (ref "DS1") (pin "16") (pinfunction "K_16") (pintype "bidirectional"))
      (node (ref "DS1") (pin "5") (pinfunction "R/W_5") (pintype "bidirectional"))
      (node (ref "IC1") (pin "1") (pinfunction "C_1") (pintype "passive"))
      (node (ref "IC10") (pin "10") (pinfunction "+IN_10") (pintype "input"))
      (node (ref "IC10") (pin "12") (pinfunction "+IN_12") (pintype "input"))
      (node (ref "IC10") (pin "3") (pinfunction "+IN_3") (pintype "input"))
      (node (ref "IC10") (pin "5") (pinfunction "+IN_5") (pintype "input"))
      (node (ref "IC2") (pin "10") (pinfunction "+IN_10") (pintype "input"))
      (node (ref "IC2") (pin "12") (pinfunction "+IN_12") (pintype "input"))
      (node (ref "IC2") (pin "3") (pinfunction "+IN_3") (pintype "input"))
      (node (ref "IC2") (pin "5") (pinfunction "+IN_5") (pintype "input"))
      (node (ref "IC3") (pin "5") (pinfunction "LDAC_5") (pintype "input"))
      (node (ref "IC3") (pin "7") (pinfunction "AVSS_7") (pintype "power_in"))
      (node (ref "IC4") (pin "1") (pinfunction "C_1") (pintype "passive"))
      (node (ref "IC5") (pin "13") (pinfunction "G_13") (pintype "input"))
      (node (ref "IC5") (pin "8") (pinfunction "GND_8") (pintype "power_in"))
      (node (ref "IC6") (pin "10") (pinfunction "SER_10") (pintype "input"))
      (node (ref "IC6") (pin "15") (pinfunction "INH_15") (pintype "input"))
      (node (ref "IC6") (pin "5") (pinfunction "G_5") (pintype "input"))
      (node (ref "IC6") (pin "6") (pinfunction "H_6") (pintype "input"))
      (node (ref "IC6") (pin "8") (pinfunction "GND_8") (pintype "power_in"))
      (node (ref "IC7") (pin "3") (pinfunction "+IN_3") (pintype "input"))
      (node (ref "IC7") (pin "4") (pinfunction "V-_4") (pintype "power_in"))
      (node (ref "IC8") (pin "1") (pinfunction "GND_1") (pintype "power_in"))
      (node (ref "IC9") (pin "18") (pinfunction "GND_18") (pintype "power_in"))
      (node (ref "IC9") (pin "28") (pinfunction "GND_28") (pintype "power_in"))
      (node (ref "IC9") (pin "39") (pinfunction "GND_39") (pintype "power_in"))
      (node (ref "IC9") (pin "6") (pinfunction "GND_6") (pintype "power_in"))
      (node (ref "J1") (pin "P1") (pinfunction "1_P1") (pintype "passive"))
      (node (ref "J10") (pin "P1") (pinfunction "1_P1") (pintype "passive"))
      (node (ref "J10") (pin "P2") (pinfunction "2_P2") (pintype "passive"))
      (node (ref "J11") (pin "P1") (pinfunction "1_P1") (pintype "passive"))
      (node (ref "J2") (pin "P1") (pinfunction "1_P1") (pintype "passive"))
      (node (ref "J3") (pin "P1") (pinfunction "1_P1") (pintype "passive"))
      (node (ref "J4") (pin "P1") (pinfunction "1_P1") (pintype "passive"))
      (node (ref "J5") (pin "P1") (pinfunction "1_P1") (pintype "passive"))
      (node (ref "J6") (pin "P1") (pinfunction "1_P1") (pintype "passive"))
      (node (ref "J7") (pin "3") (pinfunction "3_3") (pintype "passive"))
      (node (ref "J7") (pin "4") (pinfunction "4_4") (pintype "passive"))
      (node (ref "J7") (pin "5") (pinfunction "5_5") (pintype "passive"))
      (node (ref "J7") (pin "6") (pinfunction "6_6") (pintype "passive"))
      (node (ref "J7") (pin "7") (pinfunction "7_7") (pintype "passive"))
      (node (ref "J7") (pin "8") (pinfunction "8_8") (pintype "passive"))
      (node (ref "J8") (pin "P1") (pinfunction "1_P1") (pintype "passive"))
      (node (ref "J9") (pin "P1") (pinfunction "1_P1") (pintype "passive"))
      (node (ref "LED1") (pin "K") (pinfunction "C_K") (pintype "passive"))
      (node (ref "LED2") (pin "K") (pinfunction "C_K") (pintype "passive"))
      (node (ref "LED3") (pin "K") (pinfunction "C_K") (pintype "passive"))
      (node (ref "LED4") (pin "K") (pinfunction "C_K") (pintype "passive"))
      (node (ref "LED5") (pin "K") (pinfunction "C_K") (pintype "passive"))
      (node (ref "LED6") (pin "K") (pinfunction "C_K") (pintype "passive"))
      (node (ref "OK1") (pin "5") (pinfunction "GND_5") (pintype "passive"))
      (node (ref "Q1") (pin "E") (pinfunction "E_E") (pintype "passive"))
      (node (ref "R31") (pin "1") (pinfunction "1_1") (pintype "passive"))
      (node (ref "R43") (pin "3") (pinfunction "A_3") (pintype "passive"))
      (node (ref "R61") (pin "2") (pinfunction "2_2") (pintype "passive"))
      (node (ref "S1") (pin "1") (pinfunction "1_1") (pintype "passive"))
      (node (ref "S1") (pin "2") (pinfunction "2_2") (pintype "passive"))
      (node (ref "S2") (pin "1") (pinfunction "1_1") (pintype "passive"))
      (node (ref "S2") (pin "2") (pinfunction "2_2") (pintype "passive"))
      (node (ref "S3") (pin "1") (pinfunction "1_1") (pintype "passive"))
      (node (ref "S3") (pin "2") (pinfunction "2_2") (pintype "passive"))
      (node (ref "S4") (pin "1") (pinfunction "1_1") (pintype "passive"))
      (node (ref "S4") (pin "2") (pinfunction "2_2") (pintype "passive"))
      (node (ref "S5") (pin "1") (pinfunction "1_1") (pintype "passive"))
      (node (ref "S5") (pin "2") (pinfunction "2_2") (pintype "passive"))
      (node (ref "S6") (pin "1") (pinfunction "1_1") (pintype "passive"))
      (node (ref "S6") (pin "2") (pinfunction "2_2") (pintype "passive"))
      (node (ref "SW1") (pin "C") (pinfunction "C_C") (pintype "passive"))
      (node (ref "SW1") (pin "D") (pinfunction "1_D") (pintype "passive"))
      (node (ref "U1") (pin "6") (pinfunction "6_6") (pintype "passive"))
    )
    (net (code "16") (name "IO_ENABLE") (class "Default")
      (node (ref "IC5") (pin "12") (pinfunction "RCK_12") (pintype "input"))
      (node (ref "IC6") (pin "1") (pinfunction "SH/~{LD}_1") (pintype "input"))
      (node (ref "IC9") (pin "23") (pinfunction "(PCINT20/TDO)PC4_23") (pintype "output"))
    )
    (net (code "17") (name "IO_INPUT") (class "Default")
      (node (ref "IC6") (pin "9") (pinfunction "QH_9") (pintype "output"))
      (node (ref "IC9") (pin "25") (pinfunction "(PCINT22/TOSC1)PC6_25") (pintype "output"))
    )
    (net (code "18") (name "IO_OUTPUT") (class "Default")
      (node (ref "IC5") (pin "14") (pinfunction "SER_14") (pintype "input"))
      (node (ref "IC9") (pin "24") (pinfunction "(PCINT21/TDI)PC5_24") (pintype "output"))
    )
    (net (code "19") (name "IO_SCK") (class "Default")
      (node (ref "IC5") (pin "11") (pinfunction "SCK_11") (pintype "input"))
      (node (ref "IC6") (pin "2") (pinfunction "CLK_2") (pintype "input"))
      (node (ref "IC9") (pin "26") (pinfunction "(PCINT23/TOSC2)PC7_26") (pintype "output"))
    )
    (net (code "20") (name "LCD_DATA4") (class "Default")
      (node (ref "DS1") (pin "11") (pinfunction "D4_11") (pintype "bidirectional"))
      (node (ref "IC9") (pin "33") (pinfunction "(PCINT4/ADC4)PA4_33") (pintype "bidirectional"))
    )
    (net (code "21") (name "LCD_DATA5") (class "Default")
      (node (ref "DS1") (pin "12") (pinfunction "D5_12") (pintype "bidirectional"))
      (node (ref "IC9") (pin "32") (pinfunction "(PCINT5/ADC5)PA5_32") (pintype "bidirectional"))
    )
    (net (code "22") (name "LCD_DATA6") (class "Default")
      (node (ref "DS1") (pin "13") (pinfunction "D6_13") (pintype "bidirectional"))
      (node (ref "IC9") (pin "31") (pinfunction "(PCINT6/ADC6)PA6_31") (pintype "bidirectional"))
    )
    (net (code "23") (name "LCD_DATA7") (class "Default")
      (node (ref "DS1") (pin "14") (pinfunction "D7_14") (pintype "bidirectional"))
      (node (ref "IC9") (pin "30") (pinfunction "(PCINT7/ADC7)PA7_30") (pintype "bidirectional"))
    )
    (net (code "24") (name "LCD_ENABLE") (class "Default")
      (node (ref "DS1") (pin "6") (pinfunction "E_6") (pintype "bidirectional"))
      (node (ref "IC9") (pin "35") (pinfunction "(PCINT2/ADC2)PA2_35") (pintype "bidirectional"))
    )
    (net (code "25") (name "LCD_RS") (class "Default")
      (node (ref "DS1") (pin "4") (pinfunction "RS_4") (pintype "bidirectional"))
      (node (ref "IC9") (pin "34") (pinfunction "(PCINT3/ADC3)PA3_34") (pintype "bidirectional"))
    )
    (net (code "26") (name "MIDI_IN") (class "Default")
      (node (ref "IC9") (pin "9") (pinfunction "(PCINT24/RXD0)PD0_9") (pintype "bidirectional"))
      (node (ref "OK1") (pin "6") (pinfunction "VO_6") (pintype "passive"))
      (node (ref "R5") (pin "1") (pinfunction "1_1") (pintype "passive"))
    )
    (net (code "27") (name "MISO") (class "Default")
      (node (ref "IC9") (pin "2") (pinfunction "(PCINT14/MISO)PB6_2") (pintype "bidirectional"))
      (node (ref "U1") (pin "1") (pinfunction "1_1") (pintype "passive"))
    )
    (net (code "28") (name "MOSI") (class "Default")
      (node (ref "IC3") (pin "4") (pinfunction "SDI_4") (pintype "input"))
      (node (ref "IC9") (pin "1") (pinfunction "(PCINT13/MOSI)PB5_1") (pintype "bidirectional"))
      (node (ref "U1") (pin "4") (pinfunction "4_4") (pintype "passive"))
    )
    (net (code "29") (name "Net-(C6-Pad-)") (class "Default")
      (node (ref "C6") (pin "-") (pinfunction "-_-") (pintype "passive"))
      (node (ref "R11") (pin "1") (pinfunction "1_1") (pintype "passive"))
    )
    (net (code "30") (name "Net-(C24-Pad-)") (class "Default")
      (node (ref "C24") (pin "-") (pinfunction "-_-") (pintype "passive"))
      (node (ref "R29") (pin "1") (pinfunction "1_1") (pintype "passive"))
    )
    (net (code "31") (name "Net-(D2-PadA)") (class "Default")
      (node (ref "D2") (pin "A") (pinfunction "A_A") (pintype "passive"))
      (node (ref "J7") (pin "1") (pinfunction "1_1") (pintype "passive"))
      (node (ref "J7") (pin "2") (pinfunction "2_2") (pintype "passive"))
    )
    (net (code "32") (name "Net-(D3-PadC)") (class "Default")
      (node (ref "D3") (pin "C") (pinfunction "C_C") (pintype "passive"))
      (node (ref "J7") (pin "10") (pinfunction "10_10") (pintype "passive"))
      (node (ref "J7") (pin "9") (pinfunction "9_9") (pintype "passive"))
    )
    (net (code "33") (name "Net-(DS1-A)") (class "Default")
      (node (ref "DS1") (pin "15") (pinfunction "A_15") (pintype "bidirectional"))
      (node (ref "R42") (pin "2") (pinfunction "2_2") (pintype "passive"))
    )
    (net (code "34") (name "Net-(DS1-VO)") (class "Default")
      (node (ref "DS1") (pin "2") (pinfunction "VO_2") (pintype "bidirectional"))
      (node (ref "R43") (pin "2") (pinfunction "S_2") (pintype "passive"))
    )
    (net (code "35") (name "Net-(IC2A--IN)") (class "Default")
      (node (ref "IC2") (pin "2") (pinfunction "-IN_2") (pintype "input"))
      (node (ref "R53") (pin "1") (pinfunction "1_1") (pintype "passive"))
      (node (ref "R59") (pin "2") (pinfunction "2_2") (pintype "passive"))
    )
    (net (code "36") (name "Net-(IC2A-OUT)") (class "Default")
      (node (ref "IC2") (pin "1") (pinfunction "OUT_1") (pintype "output"))
      (node (ref "R51") (pin "1") (pinfunction "1_1") (pintype "passive"))
      (node (ref "R53") (pin "2") (pinfunction "2_2") (pintype "passive"))
    )
    (net (code "37") (name "Net-(IC2B--IN)") (class "Default")
      (node (ref "C7") (pin "1") (pinfunction "1_1") (pintype "passive"))
      (node (ref "IC2") (pin "6") (pinfunction "-IN_6") (pintype "input"))
      (node (ref "R11") (pin "2") (pinfunction "2_2") (pintype "passive"))
      (node (ref "R15") (pin "1") (pinfunction "1_1") (pintype "passive"))
    )
    (net (code "38") (name "Net-(IC2B-OUT)") (class "Default")
      (node (ref "IC2") (pin "7") (pinfunction "OUT_7") (pintype "output"))
      (node (ref "R35") (pin "1") (pinfunction "1_1") (pintype "passive"))
    )
    (net (code "39") (name "Net-(IC2C--IN)") (class "Default")
      (node (ref "C8") (pin "1") (pinfunction "1_1") (pintype "passive"))
      (node (ref "IC2") (pin "9") (pinfunction "-IN_9") (pintype "input"))
      (node (ref "R10") (pin "2") (pinfunction "2_2") (pintype "passive"))
      (node (ref "R12") (pin "2") (pinfunction "2_2") (pintype "passive"))
      (node (ref "R16") (pin "1") (pinfunction "1_1") (pintype "passive"))
    )
    (net (code "40") (name "Net-(IC2C-OUT)") (class "Default")
      (node (ref "IC2") (pin "8") (pinfunction "OUT_8") (pintype "output"))
      (node (ref "R34") (pin "1") (pinfunction "1_1") (pintype "passive"))
    )
    (net (code "41") (name "Net-(IC2D--IN)") (class "Default")
      (node (ref "IC2") (pin "13") (pinfunction "-IN_13") (pintype "input"))
      (node (ref "R52") (pin "1") (pinfunction "1_1") (pintype "passive"))
      (node (ref "R58") (pin "2") (pinfunction "2_2") (pintype "passive"))
    )
    (net (code "42") (name "Net-(IC2D-OUT)") (class "Default")
      (node (ref "IC2") (pin "14") (pinfunction "OUT_14") (pintype "output"))
      (node (ref "R50") (pin "1") (pinfunction "1_1") (pintype "passive"))
      (node (ref "R52") (pin "2") (pinfunction "2_2") (pintype "passive"))
    )
    (net (code "43") (name "Net-(IC5A-QA)") (class "Default")
      (node (ref "IC5") (pin "15") (pinfunction "QA_15") (pintype "tri_state"))
      (node (ref "R19") (pin "1") (pinfunction "1_1") (pintype "passive"))
    )
    (net (code "44") (name "Net-(IC5A-QB)") (class "Default")
      (node (ref "IC5") (pin "1") (pinfunction "QB_1") (pintype "tri_state"))
      (node (ref "R20") (pin "1") (pinfunction "1_1") (pintype "passive"))
    )
    (net (code "45") (name "Net-(IC5A-QC)") (class "Default")
      (node (ref "IC5") (pin "2") (pinfunction "QC_2") (pintype "tri_state"))
      (node (ref "R21") (pin "1") (pinfunction "1_1") (pintype "passive"))
    )
    (net (code "46") (name "Net-(IC5A-QD)") (class "Default")
      (node (ref "IC5") (pin "3") (pinfunction "QD_3") (pintype "tri_state"))
      (node (ref "R22") (pin "1") (pinfunction "1_1") (pintype "passive"))
    )
    (net (code "47") (name "Net-(IC5A-QE)") (class "Default")
      (node (ref "IC5") (pin "4") (pinfunction "QE_4") (pintype "tri_state"))
      (node (ref "R23") (pin "1") (pinfunction "1_1") (pintype "passive"))
    )
    (net (code "48") (name "Net-(IC5A-QF)") (class "Default")
      (node (ref "IC5") (pin "5") (pinfunction "QF_5") (pintype "tri_state"))
      (node (ref "R24") (pin "1") (pinfunction "1_1") (pintype "passive"))
    )
    (net (code "49") (name "Net-(IC6A-A)") (class "Default")
      (node (ref "IC6") (pin "11") (pinfunction "A_11") (pintype "input"))
      (node (ref "R40") (pin "1") (pinfunction "1_1") (pintype "passive"))
      (node (ref "S1") (pin "3") (pinfunction "3_3") (pintype "passive"))
      (node (ref "S1") (pin "4") (pinfunction "4_4") (pintype "passive"))
    )
    (net (code "50") (name "Net-(IC6A-B)") (class "Default")
      (node (ref "IC6") (pin "12") (pinfunction "B_12") (pintype "input"))
      (node (ref "R36") (pin "1") (pinfunction "1_1") (pintype "passive"))
      (node (ref "S2") (pin "3") (pinfunction "3_3") (pintype "passive"))
      (node (ref "S2") (pin "4") (pinfunction "4_4") (pintype "passive"))
    )
    (net (code "51") (name "Net-(IC6A-C)") (class "Default")
      (node (ref "IC6") (pin "13") (pinfunction "C_13") (pintype "input"))
      (node (ref "R37") (pin "1") (pinfunction "1_1") (pintype "passive"))
      (node (ref "S3") (pin "3") (pinfunction "3_3") (pintype "passive"))
      (node (ref "S3") (pin "4") (pinfunction "4_4") (pintype "passive"))
    )
    (net (code "52") (name "Net-(IC6A-D)") (class "Default")
      (node (ref "IC6") (pin "14") (pinfunction "D_14") (pintype "input"))
      (node (ref "R38") (pin "1") (pinfunction "1_1") (pintype "passive"))
      (node (ref "S4") (pin "3") (pinfunction "3_3") (pintype "passive"))
      (node (ref "S4") (pin "4") (pinfunction "4_4") (pintype "passive"))
    )
    (net (code "53") (name "Net-(IC6A-E)") (class "Default")
      (node (ref "IC6") (pin "3") (pinfunction "E_3") (pintype "input"))
      (node (ref "R39") (pin "1") (pinfunction "1_1") (pintype "passive"))
      (node (ref "S5") (pin "3") (pinfunction "3_3") (pintype "passive"))
      (node (ref "S5") (pin "4") (pinfunction "4_4") (pintype "passive"))
    )
    (net (code "54") (name "Net-(IC6A-F)") (class "Default")
      (node (ref "IC6") (pin "4") (pinfunction "F_4") (pintype "input"))
      (node (ref "R41") (pin "1") (pinfunction "1_1") (pintype "passive"))
      (node (ref "S6") (pin "3") (pinfunction "3_3") (pintype "passive"))
      (node (ref "S6") (pin "4") (pinfunction "4_4") (pintype "passive"))
    )
    (net (code "55") (name "Net-(IC7A--IN)") (class "Default")
      (node (ref "IC7") (pin "2") (pinfunction "-IN_2") (pintype "input"))
      (node (ref "R30") (pin "1") (pinfunction "1_1") (pintype "passive"))
      (node (ref "R32") (pin "2") (pinfunction "2_2") (pintype "passive"))
    )
    (net (code "56") (name "Net-(IC7B-+IN)") (class "Default")
      (node (ref "C25") (pin "1") (pinfunction "1_1") (pintype "passive"))
      (node (ref "IC7") (pin "5") (pinfunction "+IN_5") (pintype "input"))
      (node (ref "R31") (pin "2") (pinfunction "2_2") (pintype "passive"))
      (node (ref "R33") (pin "1") (pinfunction "1_1") (pintype "passive"))
    )
    (net (code "57") (name "Net-(IC7B--IN)") (class "Default")
      (node (ref "C22") (pin "1") (pinfunction "1_1") (pintype "passive"))
      (node (ref "IC7") (pin "6") (pinfunction "-IN_6") (pintype "input"))
      (node (ref "R28") (pin "1") (pinfunction "1_1") (pintype "passive"))
      (node (ref "R29") (pin "2") (pinfunction "2_2") (pintype "passive"))
    )
    (net (code "58") (name "Net-(IC9-AREF)") (class "Default")
      (node (ref "C18") (pin "1") (pinfunction "1_1") (pintype "passive"))
      (node (ref "IC9") (pin "29") (pinfunction "AREF_29") (pintype "passive"))
    )
    (net (code "59") (name "Net-(IC9-XTAL1)") (class "Default")
      (node (ref "C13") (pin "2") (pinfunction "2_2") (pintype "passive"))
      (node (ref "IC9") (pin "8") (pinfunction "XTAL1_8") (pintype "bidirectional"))
      (node (ref "Q2") (pin "1") (pinfunction "1_1") (pintype "passive"))
    )
    (net (code "60") (name "Net-(IC9-XTAL2)") (class "Default")
      (node (ref "C14") (pin "2") (pinfunction "2_2") (pintype "passive"))
      (node (ref "IC9") (pin "7") (pinfunction "XTAL2_7") (pintype "bidirectional"))
      (node (ref "Q2") (pin "2") (pinfunction "2_2") (pintype "passive"))
    )
    (net (code "61") (name "Net-(IC10A--IN)") (class "Default")
      (node (ref "IC10") (pin "2") (pinfunction "-IN_2") (pintype "input"))
      (node (ref "R14") (pin "1") (pinfunction "1_1") (pintype "passive"))
      (node (ref "R45") (pin "2") (pinfunction "2_2") (pintype "passive"))
    )
    (net (code "62") (name "Net-(IC10B--IN)") (class "Default")
      (node (ref "IC10") (pin "6") (pinfunction "-IN_6") (pintype "input"))
      (node (ref "R4") (pin "1") (pinfunction "1_1") (pintype "passive"))
      (node (ref "R44") (pin "2") (pinfunction "2_2") (pintype "passive"))
    )
    (net (code "63") (name "Net-(IC10C--IN)") (class "Default")
      (node (ref "IC10") (pin "9") (pinfunction "-IN_9") (pintype "input"))
      (node (ref "R46") (pin "1") (pinfunction "1_1") (pintype "passive"))
      (node (ref "R56") (pin "2") (pinfunction "2_2") (pintype "passive"))
    )
    (net (code "64") (name "Net-(IC10C-OUT)") (class "Default")
      (node (ref "IC10") (pin "8") (pinfunction "OUT_8") (pintype "output"))
      (node (ref "R46") (pin "2") (pinfunction "2_2") (pintype "passive"))
      (node (ref "R48") (pin "1") (pinfunction "1_1") (pintype "passive"))
    )
    (net (code "65") (name "Net-(IC10D--IN)") (class "Default")
      (node (ref "IC10") (pin "13") (pinfunction "-IN_13") (pintype "input"))
      (node (ref "R47") (pin "1") (pinfunction "1_1") (pintype "passive"))
      (node (ref "R57") (pin "2") (pinfunction "2_2") (pintype "passive"))
    )
    (net (code "66") (name "Net-(IC10D-OUT)") (class "Default")
      (node (ref "IC10") (pin "14") (pinfunction "OUT_14") (pintype "output"))
      (node (ref "R47") (pin "2") (pinfunction "2_2") (pintype "passive"))
      (node (ref "R49") (pin "1") (pinfunction "1_1") (pintype "passive"))
    )
    (net (code "67") (name "Net-(J1-3)") (class "Default")
      (node (ref "J1") (pin "P3") (pinfunction "3_P3") (pintype "passive"))
      (node (ref "R25") (pin "2") (pinfunction "2_2") (pintype "passive"))
    )
    (net (code "68") (name "Net-(J2-3)") (class "Default")
      (node (ref "J2") (pin "P3") (pinfunction "3_P3") (pintype "passive"))
      (node (ref "R27") (pin "2") (pinfunction "2_2") (pintype "passive"))
    )
    (net (code "69") (name "Net-(J3-3)") (class "Default")
      (node (ref "C8") (pin "2") (pinfunction "2_2") (pintype "passive"))
      (node (ref "J3") (pin "P3") (pinfunction "3_P3") (pintype "passive"))
      (node (ref "R16") (pin "2") (pinfunction "2_2") (pintype "passive"))
      (node (ref "R34") (pin "2") (pinfunction "2_2") (pintype "passive"))
    )
    (net (code "70") (name "Net-(J4-3)") (class "Default")
      (node (ref "C7") (pin "2") (pinfunction "2_2") (pintype "passive"))
      (node (ref "J4") (pin "P3") (pinfunction "3_P3") (pintype "passive"))
      (node (ref "R15") (pin "2") (pinfunction "2_2") (pintype "passive"))
      (node (ref "R35") (pin "2") (pinfunction "2_2") (pintype "passive"))
    )
    (net (code "71") (name "Net-(J5-3)") (class "Default")
      (node (ref "C24") (pin "+") (pinfunction "+_+") (pintype "passive"))
      (node (ref "J5") (pin "P3") (pinfunction "3_P3") (pintype "passive"))
      (node (ref "R32") (pin "1") (pinfunction "1_1") (pintype "passive"))
    )
    (net (code "72") (name "Net-(J6-3)") (class "Default")
      (node (ref "J6") (pin "P3") (pinfunction "3_P3") (pintype "passive"))
      (node (ref "R48") (pin "2") (pinfunction "2_2") (pintype "passive"))
    )
    (net (code "73") (name "Net-(J8-3)") (class "Default")
      (node (ref "J8") (pin "P3") (pinfunction "3_P3") (pintype "passive"))
      (node (ref "R49") (pin "2") (pinfunction "2_2") (pintype "passive"))
    )
    (net (code "74") (name "Net-(J9-3)") (class "Default")
      (node (ref "J9") (pin "P3") (pinfunction "3_P3") (pintype "passive"))
      (node (ref "R50") (pin "2") (pinfunction "2_2") (pintype "passive"))
    )
    (net (code "75") (name "Net-(J10-3)") (class "Default")
      (node (ref "J10") (pin "P3") (pinfunction "3_P3") (pintype "passive"))
      (node (ref "R18") (pin "1") (pinfunction "1_1") (pintype "passive"))
    )
    (net (code "76") (name "Net-(J11-3)") (class "Default")
      (node (ref "J11") (pin "P3") (pinfunction "3_P3") (pintype "passive"))
      (node (ref "R51") (pin "2") (pinfunction "2_2") (pintype "passive"))
    )
    (net (code "77") (name "Net-(LED1-PadA)") (class "Default")
      (node (ref "LED1") (pin "A") (pinfunction "A_A") (pintype "passive"))
      (node (ref "R19") (pin "2") (pinfunction "2_2") (pintype "passive"))
    )
    (net (code "78") (name "Net-(LED2-PadA)") (class "Default")
      (node (ref "LED2") (pin "A") (pinfunction "A_A") (pintype "passive"))
      (node (ref "R20") (pin "2") (pinfunction "2_2") (pintype "passive"))
    )
    (net (code "79") (name "Net-(LED3-PadA)") (class "Default")
      (node (ref "LED3") (pin "A") (pinfunction "A_A") (pintype "passive"))
      (node (ref "R21") (pin "2") (pinfunction "2_2") (pintype "passive"))
    )
    (net (code "80") (name "Net-(LED4-PadA)") (class "Default")
      (node (ref "LED4") (pin "A") (pinfunction "A_A") (pintype "passive"))
      (node (ref "R22") (pin "2") (pinfunction "2_2") (pintype "passive"))
    )
    (net (code "81") (name "Net-(LED5-PadA)") (class "Default")
      (node (ref "LED5") (pin "A") (pinfunction "A_A") (pintype "passive"))
      (node (ref "R23") (pin "2") (pinfunction "2_2") (pintype "passive"))
    )
    (net (code "82") (name "Net-(LED6-PadA)") (class "Default")
      (node (ref "LED6") (pin "A") (pinfunction "A_A") (pintype "passive"))
      (node (ref "R24") (pin "2") (pinfunction "2_2") (pintype "passive"))
    )
    (net (code "83") (name "Net-(OK1-A)") (class "Default")
      (node (ref "D1") (pin "C") (pinfunction "C_C") (pintype "passive"))
      (node (ref "OK1") (pin "2") (pinfunction "A_2") (pintype "passive"))
      (node (ref "R3") (pin "2") (pinfunction "2_2") (pintype "passive"))
    )
    (net (code "84") (name "Net-(OK1-C)") (class "Default")
      (node (ref "D1") (pin "A") (pinfunction "A_A") (pintype "passive"))
      (node (ref "OK1") (pin "3") (pinfunction "C_3") (pintype "passive"))
      (node (ref "U$1") (pin "P2") (pinfunction "2_P2") (pintype "passive"))
    )
    (net (code "85") (name "Net-(Q1-PadB)") (class "Default")
      (node (ref "Q1") (pin "B") (pinfunction "B_B") (pintype "passive"))
      (node (ref "R18") (pin "2") (pinfunction "2_2") (pintype "passive"))
    )
    (net (code "86") (name "Net-(R7-S)") (class "Default")
      (node (ref "R56") (pin "1") (pinfunction "1_1") (pintype "passive"))
      (node (ref "R7") (pin "2") (pinfunction "S_2") (pintype "passive"))
    )
    (net (code "87") (name "Net-(R8-S)") (class "Default")
      (node (ref "R57") (pin "1") (pinfunction "1_1") (pintype "passive"))
      (node (ref "R8") (pin "2") (pinfunction "S_2") (pintype "passive"))
    )
    (net (code "88") (name "Net-(R9-E)") (class "Default")
      (node (ref "R6") (pin "1") (pinfunction "1_1") (pintype "passive"))
      (node (ref "R9") (pin "1") (pinfunction "E_1") (pintype "passive"))
    )
    (net (code "89") (name "Net-(R10-Pad1)") (class "Default")
      (node (ref "R10") (pin "1") (pinfunction "1_1") (pintype "passive"))
      (node (ref "R6") (pin "2") (pinfunction "2_2") (pintype "passive"))
    )
    (net (code "90") (name "Net-(R13-E)") (class "Default")
      (node (ref "R12") (pin "1") (pinfunction "1_1") (pintype "passive"))
      (node (ref "R13") (pin "1") (pinfunction "E_1") (pintype "passive"))
    )
    (net (code "91") (name "Net-(R42-Pad1)") (class "Default")
      (node (ref "R42") (pin "1") (pinfunction "1_1") (pintype "passive"))
      (node (ref "R60") (pin "2") (pinfunction "2_2") (pintype "passive"))
      (node (ref "R61") (pin "1") (pinfunction "1_1") (pintype "passive"))
    )
    (net (code "92") (name "Net-(R54-S)") (class "Default")
      (node (ref "R54") (pin "2") (pinfunction "S_2") (pintype "passive"))
      (node (ref "R58") (pin "1") (pinfunction "1_1") (pintype "passive"))
    )
    (net (code "93") (name "Net-(R55-S)") (class "Default")
      (node (ref "R55") (pin "2") (pinfunction "S_2") (pintype "passive"))
      (node (ref "R59") (pin "1") (pinfunction "1_1") (pintype "passive"))
    )
    (net (code "94") (name "Net-(U$1-3)") (class "Default")
      (node (ref "R3") (pin "1") (pinfunction "1_1") (pintype "passive"))
      (node (ref "U$1") (pin "P3") (pinfunction "3_P3") (pintype "passive"))
    )
    (net (code "95") (name "PITCH_DETECTOR") (class "Default")
      (node (ref "IC7") (pin "1") (pinfunction "OUT_1") (pintype "output"))
      (node (ref "IC9") (pin "15") (pinfunction "(PCINT30/OC2B/ICP)PD6_15") (pintype "bidirectional"))
      (node (ref "R30") (pin "2") (pinfunction "2_2") (pintype "passive"))
    )
    (net (code "96") (name "REF_-4.096") (class "Default")
      (node (ref "C3") (pin "1") (pinfunction "1_1") (pintype "passive"))
      (node (ref "IC1") (pin "2") (pinfunction "A_2") (pintype "passive"))
      (node (ref "R2") (pin "2") (pinfunction "2_2") (pintype "passive"))
      (node (ref "R9") (pin "2") (pinfunction "S_2") (pintype "passive"))
      (node (ref "R9") (pin "3") (pinfunction "A_3") (pintype "passive"))
    )
    (net (code "97") (name "REF_-5V") (class "Default")
      (node (ref "C1") (pin "1") (pinfunction "1_1") (pintype "passive"))
      (node (ref "IC4") (pin "2") (pinfunction "A_2") (pintype "passive"))
      (node (ref "R1") (pin "2") (pinfunction "2_2") (pintype "passive"))
      (node (ref "R45") (pin "1") (pinfunction "1_1") (pintype "passive"))
    )
    (net (code "98") (name "RESET") (class "Default")
      (node (ref "C20") (pin "1") (pinfunction "1_1") (pintype "passive"))
      (node (ref "IC9") (pin "4") (pinfunction "RESET_4") (pintype "input"))
      (node (ref "R26") (pin "1") (pinfunction "1_1") (pintype "passive"))
      (node (ref "U1") (pin "5") (pinfunction "5_5") (pintype "passive"))
    )
    (net (code "99") (name "SCK") (class "Default")
      (node (ref "IC3") (pin "3") (pinfunction "SCK_3") (pintype "input"))
      (node (ref "IC9") (pin "3") (pinfunction "(PCINT15/SCK)PB7_3") (pintype "bidirectional"))
      (node (ref "U1") (pin "3") (pinfunction "3_3") (pintype "passive"))
    )
    (net (code "100") (name "SS") (class "Default")
      (node (ref "IC3") (pin "2") (pinfunction "#CS_2") (pintype "input"))
      (node (ref "IC9") (pin "44") (pinfunction "(PCINT12/OC0B/~{SS})PB4_44") (pintype "bidirectional"))
    )
    (net (code "101") (name "VCC") (class "Default")
      (node (ref "C12") (pin "+") (pinfunction "+_+") (pintype "passive"))
      (node (ref "C19") (pin "+") (pinfunction "+_+") (pintype "passive"))
      (node (ref "C28") (pin "1") (pinfunction "1_1") (pintype "passive"))
      (node (ref "C4") (pin "1") (pinfunction "1_1") (pintype "passive"))
      (node (ref "D2") (pin "C") (pinfunction "C_C") (pintype "passive"))
      (node (ref "IC10") (pin "4") (pinfunction "V+_4") (pintype "power_in"))
      (node (ref "IC2") (pin "4") (pinfunction "V+_4") (pintype "power_in"))
      (node (ref "IC8") (pin "3") (pinfunction "VIN_3") (pintype "input"))
    )
    (net (code "102") (name "VEE") (class "Default")
      (node (ref "C10") (pin "-") (pinfunction "-_-") (pintype "passive"))
      (node (ref "C29") (pin "2") (pinfunction "2_2") (pintype "passive"))
      (node (ref "C5") (pin "2") (pinfunction "2_2") (pintype "passive"))
      (node (ref "D3") (pin "A") (pinfunction "A_A") (pintype "passive"))
      (node (ref "IC10") (pin "11") (pinfunction "V-_11") (pintype "power_in"))
      (node (ref "IC2") (pin "11") (pinfunction "V-_11") (pintype "power_in"))
      (node (ref "R1") (pin "1") (pinfunction "1_1") (pintype "passive"))
      (node (ref "R2") (pin "1") (pinfunction "1_1") (pintype "passive"))
    )
    (net (code "103") (name "unconnected-(DS1-D0-Pad7)") (class "Default")
      (node (ref "DS1") (pin "7") (pinfunction "D0_7") (pintype "bidirectional"))
    )
    (net (code "104") (name "unconnected-(DS1-D1-Pad8)") (class "Default")
      (node (ref "DS1") (pin "8") (pinfunction "D1_8") (pintype "bidirectional"))
    )
    (net (code "105") (name "unconnected-(DS1-D2-Pad9)") (class "Default")
      (node (ref "DS1") (pin "9") (pinfunction "D2_9") (pintype "bidirectional"))
    )
    (net (code "106") (name "unconnected-(DS1-D3-Pad10)") (class "Default")
      (node (ref "DS1") (pin "10") (pinfunction "D3_10") (pintype "bidirectional"))
    )
    (net (code "107") (name "unconnected-(IC5A-QG-Pad6)") (class "Default")
      (node (ref "IC5") (pin "6") (pinfunction "QG_6") (pintype "tri_state"))
    )
    (net (code "108") (name "unconnected-(IC5A-QH*-Pad9)") (class "Default")
      (node (ref "IC5") (pin "9") (pinfunction "QH*_9") (pintype "tri_state"))
    )
    (net (code "109") (name "unconnected-(IC5A-QH-Pad7)") (class "Default")
      (node (ref "IC5") (pin "7") (pinfunction "QH_7") (pintype "tri_state"))
    )
    (net (code "110") (name "unconnected-(IC6A-~{QH}-Pad7)") (class "Default")
      (node (ref "IC6") (pin "7") (pinfunction "~{QH}_7") (pintype "output"))
    )
    (net (code "111") (name "unconnected-(IC9-(PCINT1{slash}ADC1)PA1-Pad36)") (class "Default")
      (node (ref "IC9") (pin "36") (pinfunction "(PCINT1/ADC1)PA1_36") (pintype "bidirectional"))
    )
    (net (code "112") (name "unconnected-(IC9-(PCINT8{slash}XCK0{slash}T0)PB0-Pad40)") (class "Default")
      (node (ref "IC9") (pin "40") (pinfunction "(PCINT8/XCK0/T0)PB0_40") (pintype "bidirectional"))
    )
    (net (code "113") (name "unconnected-(IC9-(PCINT9{slash}CLKO{slash}T1)PB1-Pad41)") (class "Default")
      (node (ref "IC9") (pin "41") (pinfunction "(PCINT9/CLKO/T1)PB1_41") (pintype "bidirectional"))
    )
    (net (code "114") (name "unconnected-(IC9-(PCINT10{slash}INT2{slash}AIN0)PB2-Pad42)") (class "Default")
      (node (ref "IC9") (pin "42") (pinfunction "(PCINT10/INT2/AIN0)PB2_42") (pintype "bidirectional"))
    )
    (net (code "115") (name "unconnected-(IC9-(PCINT11{slash}OC0A{slash}AIN1)PB3-Pad43)") (class "Default")
      (node (ref "IC9") (pin "43") (pinfunction "(PCINT11/OC0A/AIN1)PB3_43") (pintype "bidirectional"))
    )
    (net (code "116") (name "unconnected-(IC9-(PCINT19{slash}TMS)PC3-Pad22)") (class "Default")
      (node (ref "IC9") (pin "22") (pinfunction "(PCINT19/TMS)PC3_22") (pintype "output"))
    )
    (net (code "117") (name "unconnected-(IC9-(PCINT25{slash}TXD0)PD1-Pad10)") (class "Default")
      (node (ref "IC9") (pin "10") (pinfunction "(PCINT25/TXD0)PD1_10") (pintype "bidirectional"))
    )
    (net (code "118") (name "unconnected-(IC9-(PCINT29{slash}OC1A)PD5-Pad14)") (class "Default")
      (node (ref "IC9") (pin "14") (pinfunction "(PCINT29/OC1A)PD5_14") (pintype "bidirectional"))
    )
    (net (code "119") (name "unconnected-(IC9-(PCINT31{slash}OC2A)PD7-Pad16)") (class "Default")
      (node (ref "IC9") (pin "16") (pinfunction "(PCINT31/OC2A)PD7_16") (pintype "bidirectional"))
    )
    (net (code "120") (name "unconnected-(J1-2-PadP2)") (class "Default")
      (node (ref "J1") (pin "P2") (pinfunction "2_P2") (pintype "passive"))
    )
    (net (code "121") (name "unconnected-(J2-2-PadP2)") (class "Default")
      (node (ref "J2") (pin "P2") (pinfunction "2_P2") (pintype "passive"))
    )
    (net (code "122") (name "unconnected-(J3-2-PadP2)") (class "Default")
      (node (ref "J3") (pin "P2") (pinfunction "2_P2") (pintype "passive"))
    )
    (net (code "123") (name "unconnected-(J4-2-PadP2)") (class "Default")
      (node (ref "J4") (pin "P2") (pinfunction "2_P2") (pintype "passive"))
    )
    (net (code "124") (name "unconnected-(J5-2-PadP2)") (class "Default")
      (node (ref "J5") (pin "P2") (pinfunction "2_P2") (pintype "passive"))
    )
    (net (code "125") (name "unconnected-(J6-2-PadP2)") (class "Default")
      (node (ref "J6") (pin "P2") (pinfunction "2_P2") (pintype "passive"))
    )
    (net (code "126") (name "unconnected-(J8-2-PadP2)") (class "Default")
      (node (ref "J8") (pin "P2") (pinfunction "2_P2") (pintype "passive"))
    )
    (net (code "127") (name "unconnected-(J9-2-PadP2)") (class "Default")
      (node (ref "J9") (pin "P2") (pinfunction "2_P2") (pintype "passive"))
    )
    (net (code "128") (name "unconnected-(J11-2-PadP2)") (class "Default")
      (node (ref "J11") (pin "P2") (pinfunction "2_P2") (pintype "passive"))
    )
    (net (code "129") (name "unconnected-(OK1-VE-Pad7)") (class "Default")
      (node (ref "OK1") (pin "7") (pinfunction "VE_7") (pintype "passive"))
    )
    (net (code "130") (name "unconnected-(U$1-1-PadP1)") (class "Default")
      (node (ref "U$1") (pin "P1") (pinfunction "1_P1") (pintype "passive"))
    )
  )
)
